# tarjeta-v7.net
KiCad netlist of a schematic drawn in EAGLE
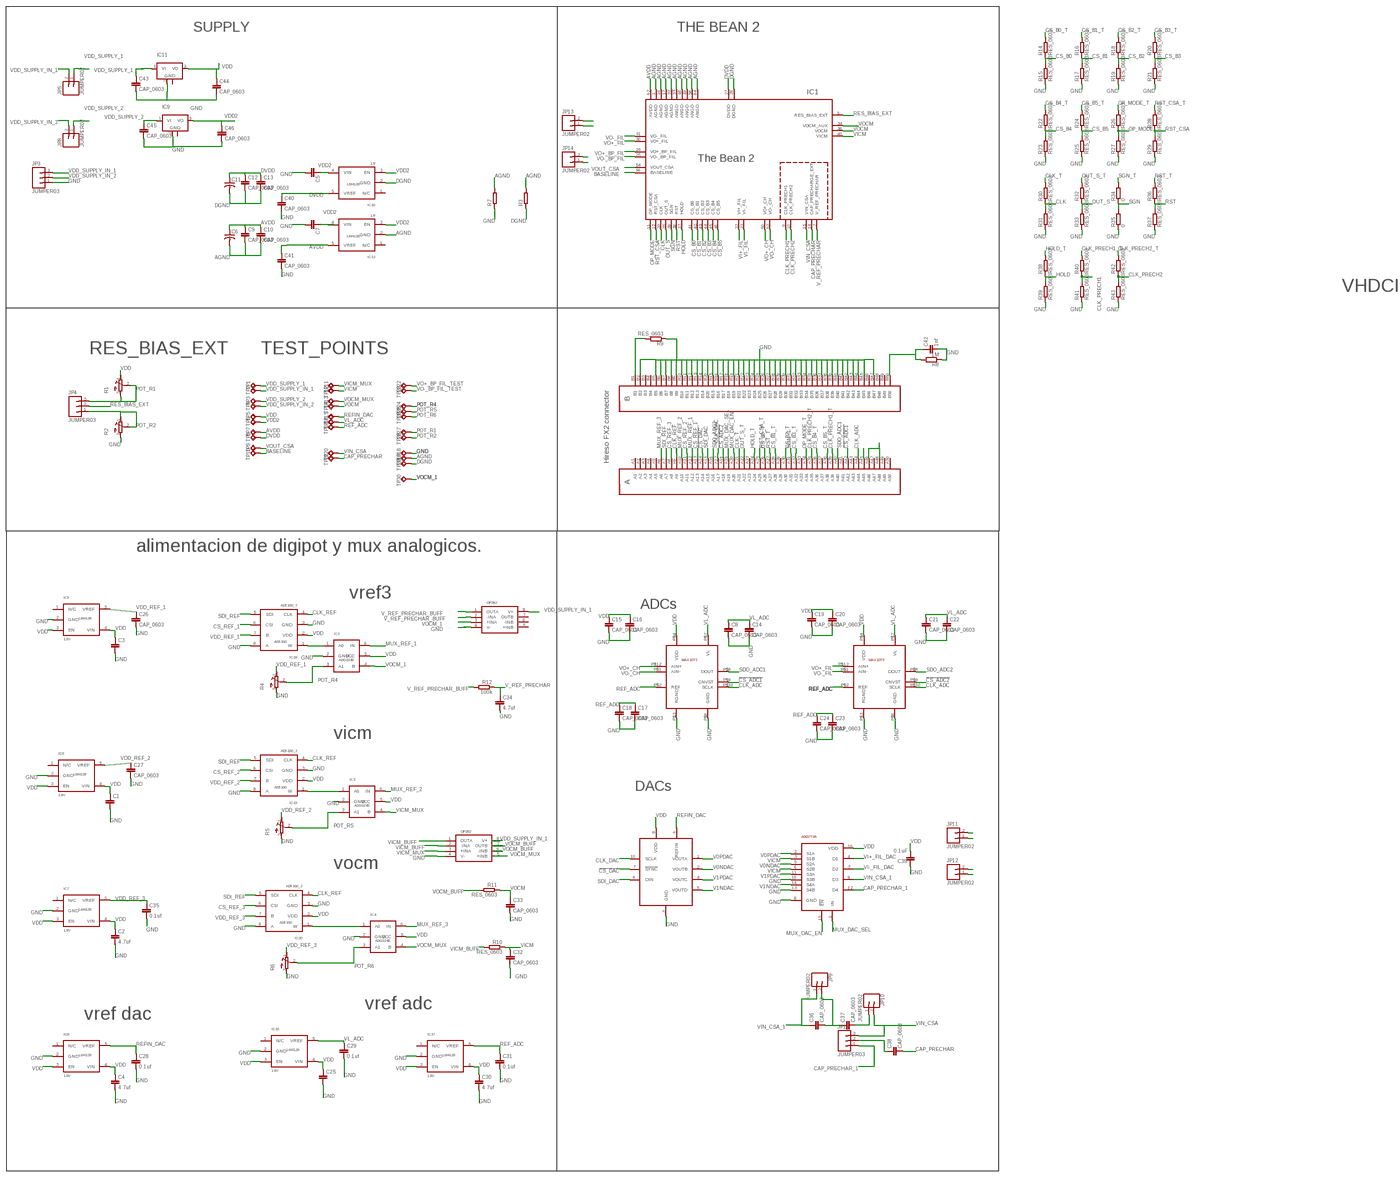
[diagram p0: schematic, sheet 1, overview]
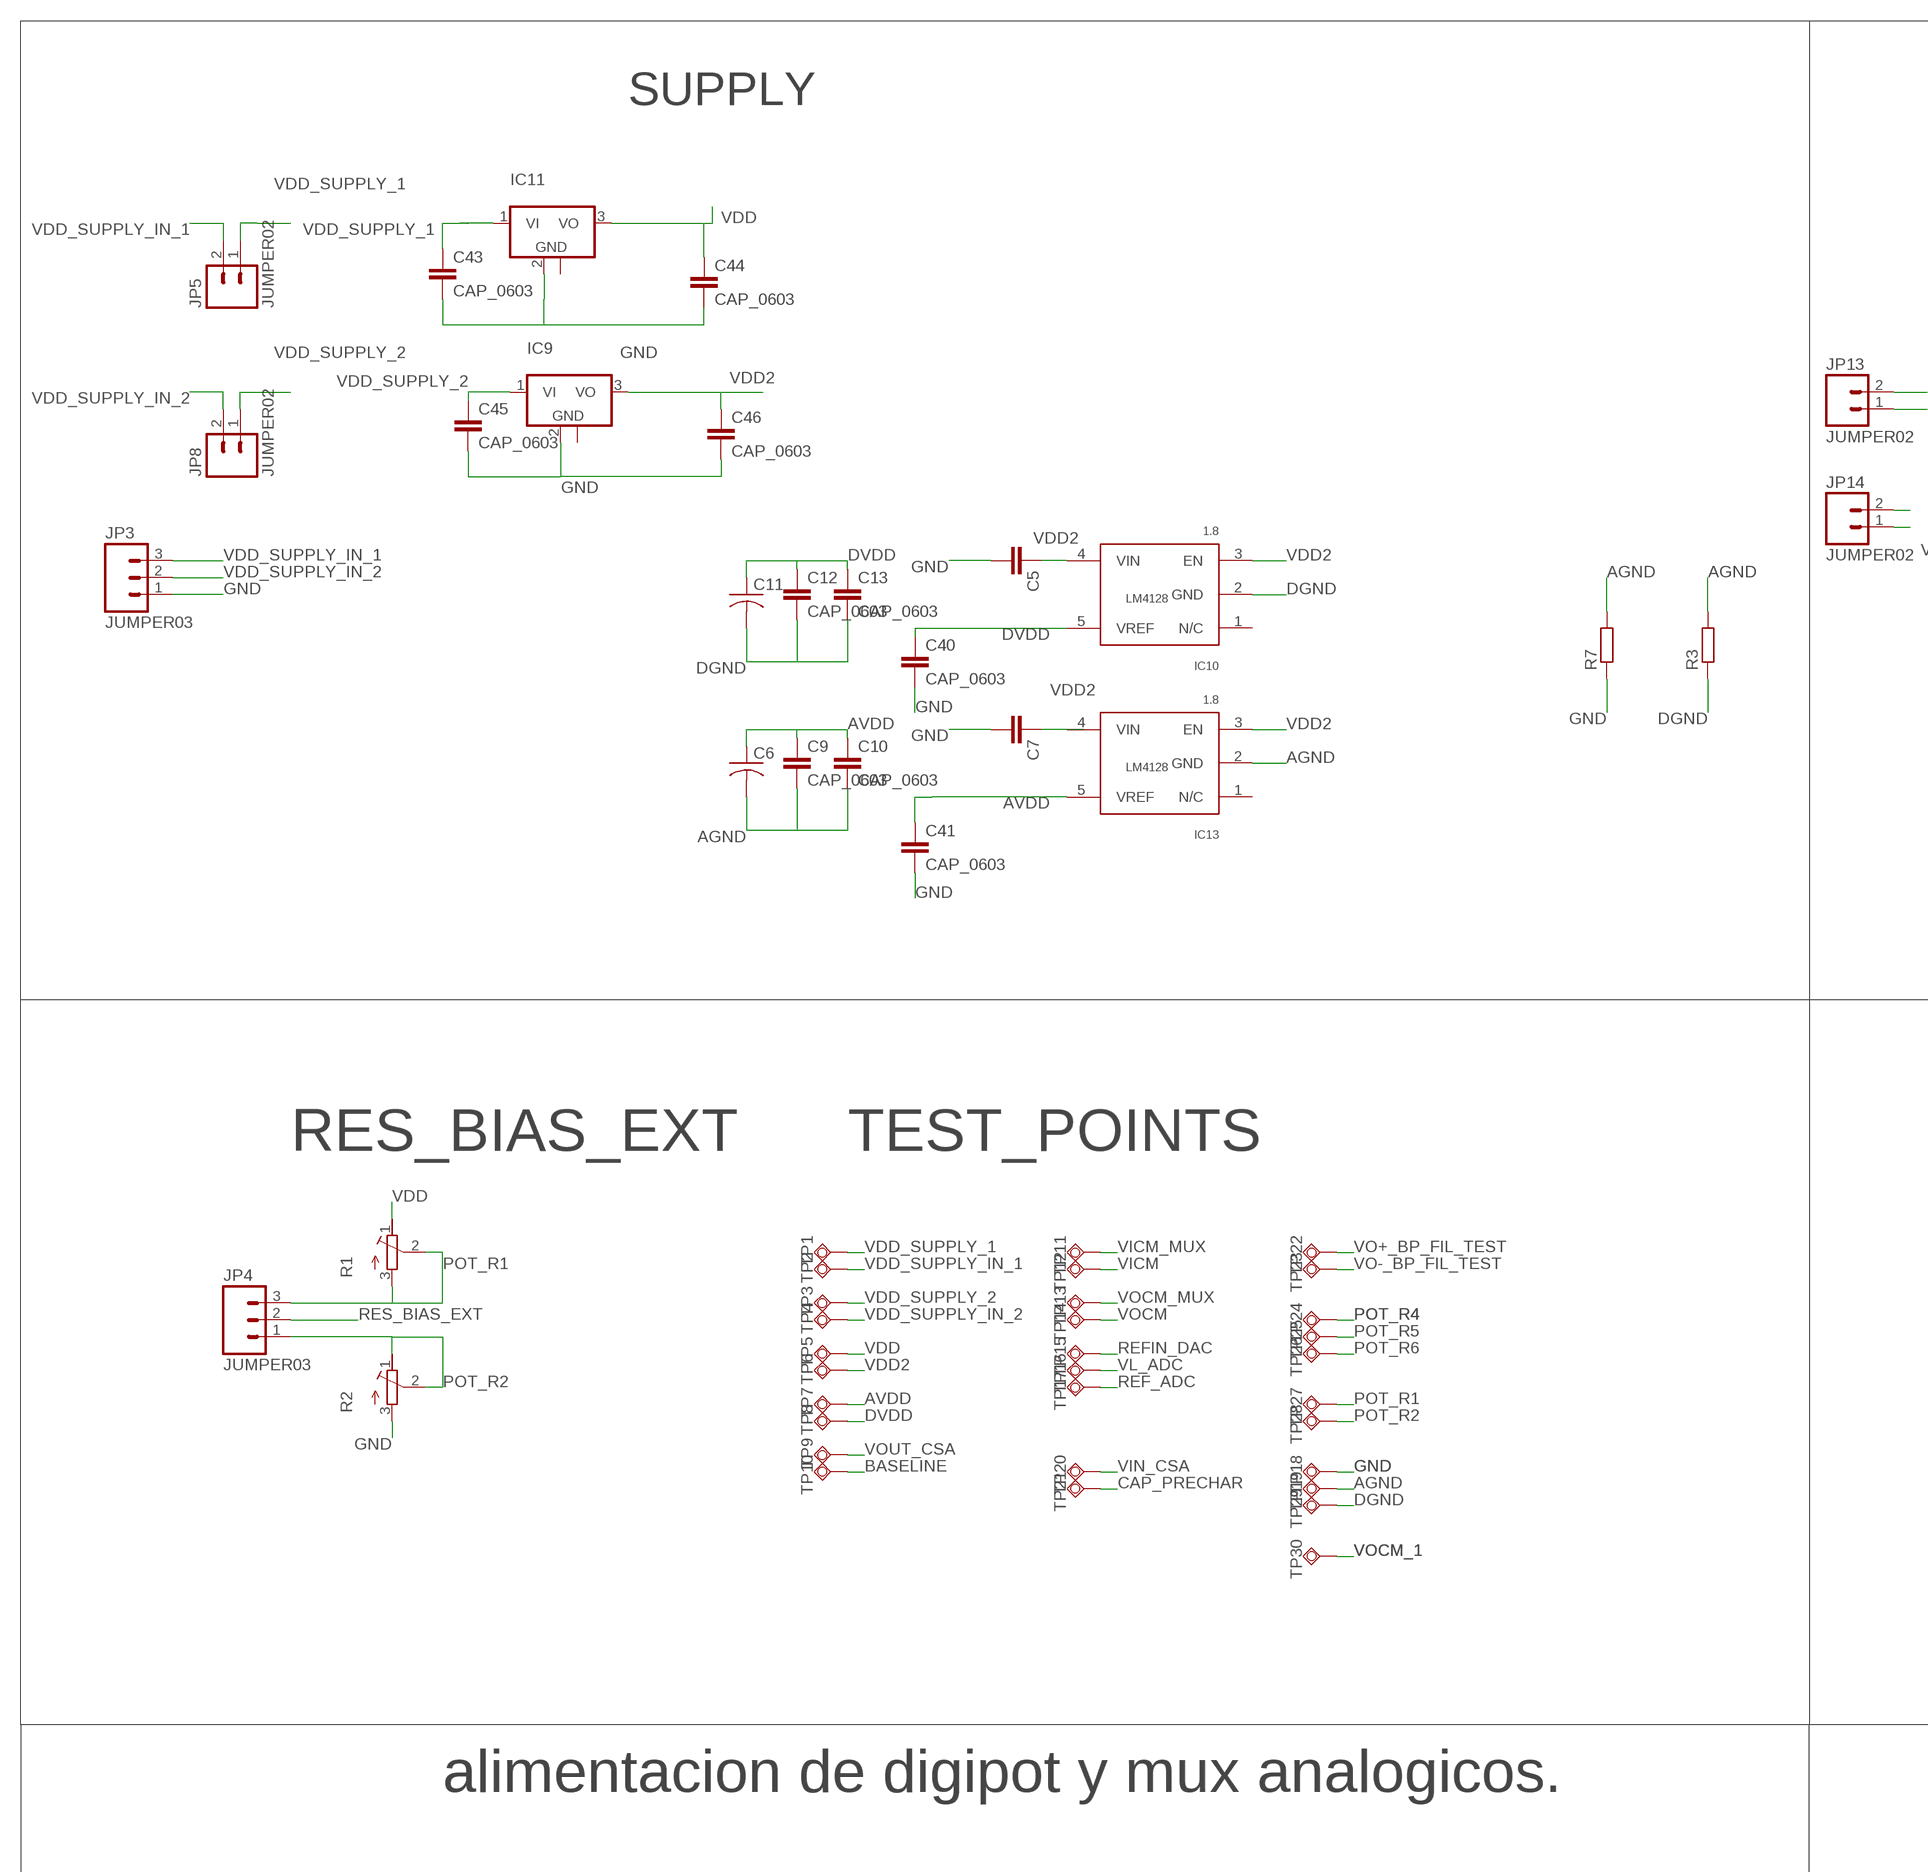
[diagram p1: schematic, sheet 1, part 1 of 4]
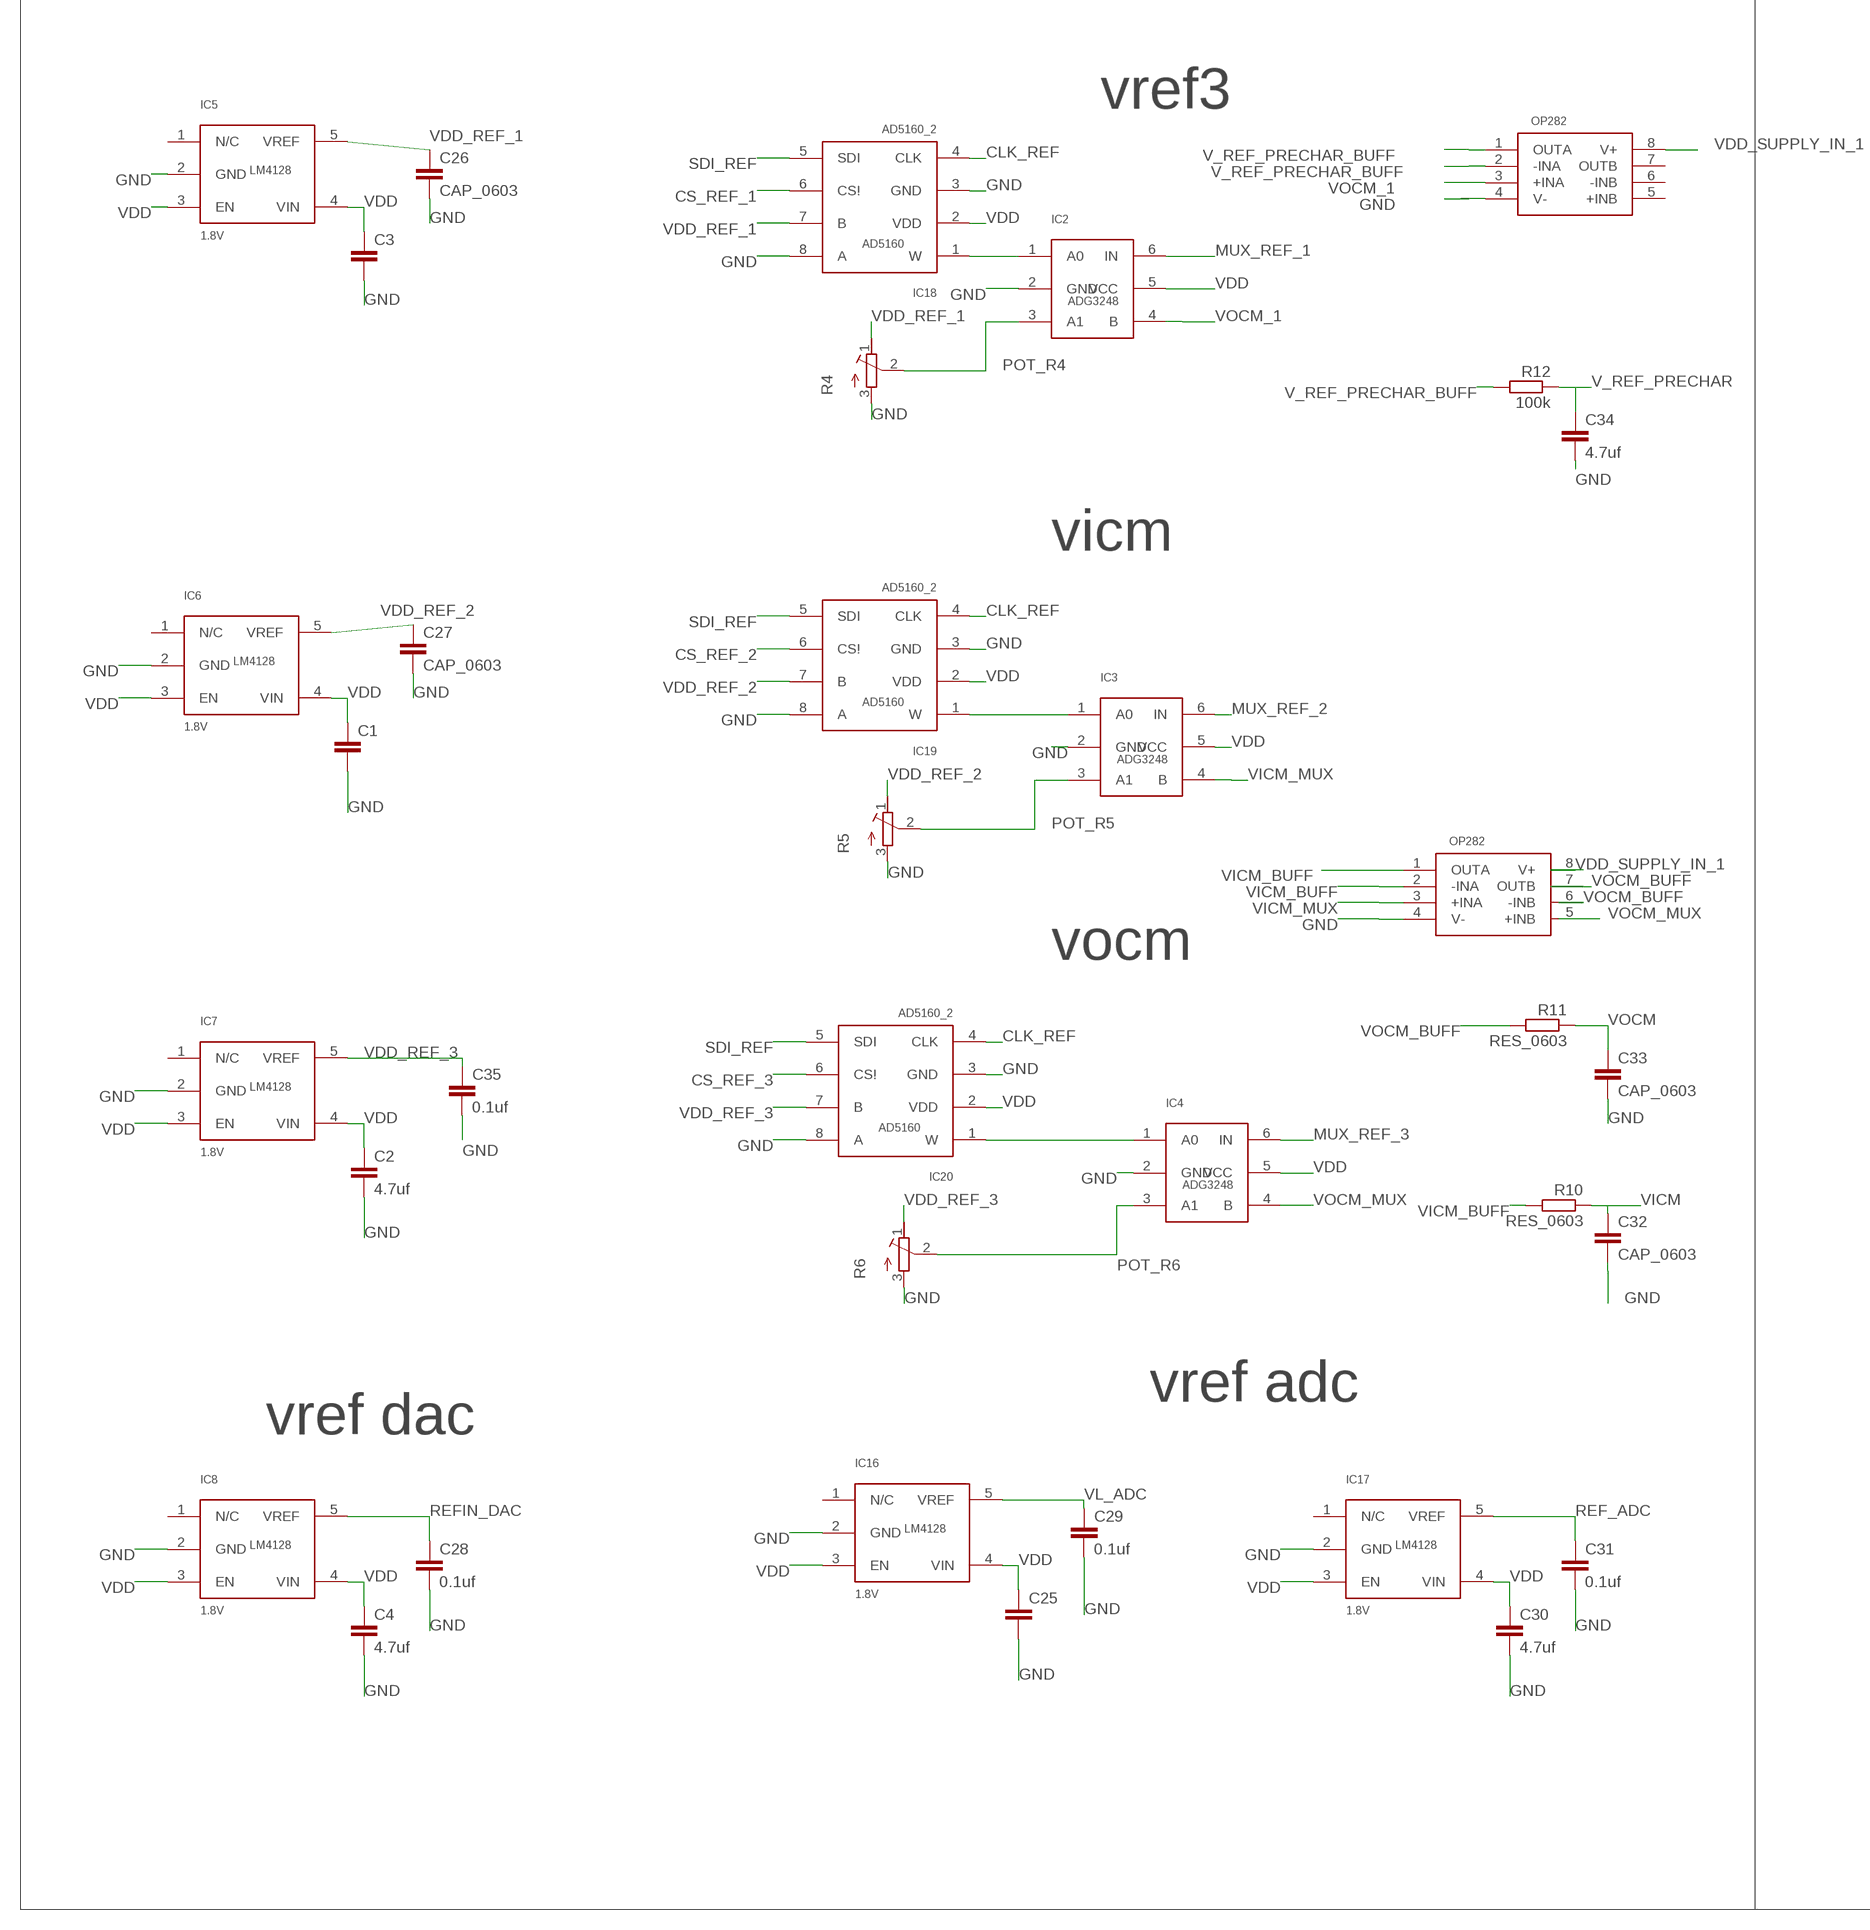
[diagram p2: schematic, sheet 1, part 2 of 4]
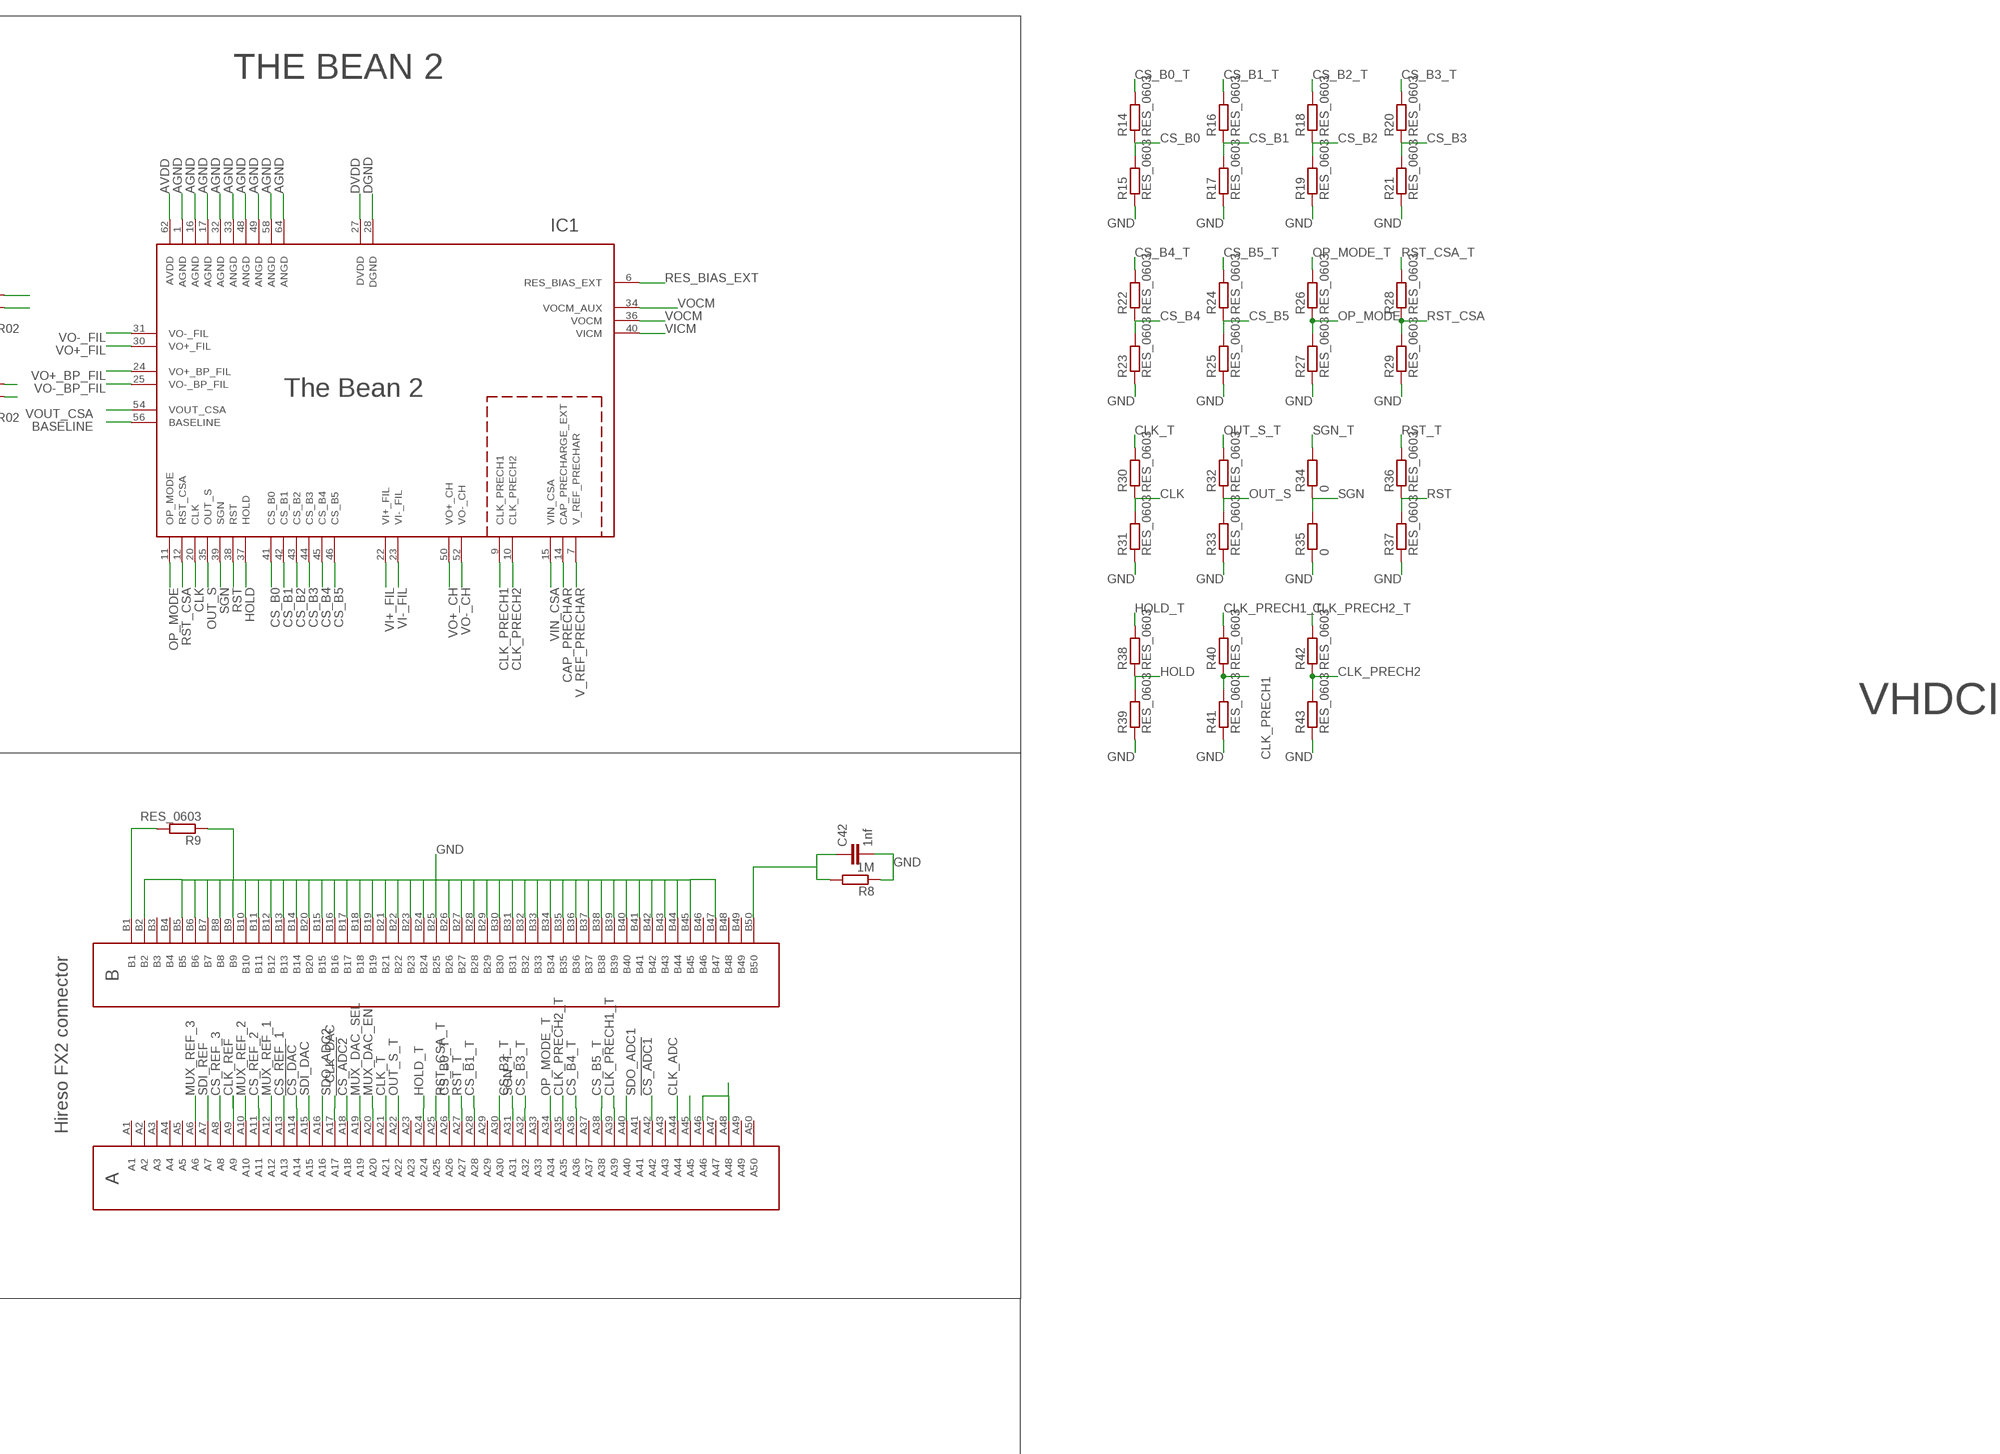
[diagram p3: schematic, sheet 1, part 3 of 4]
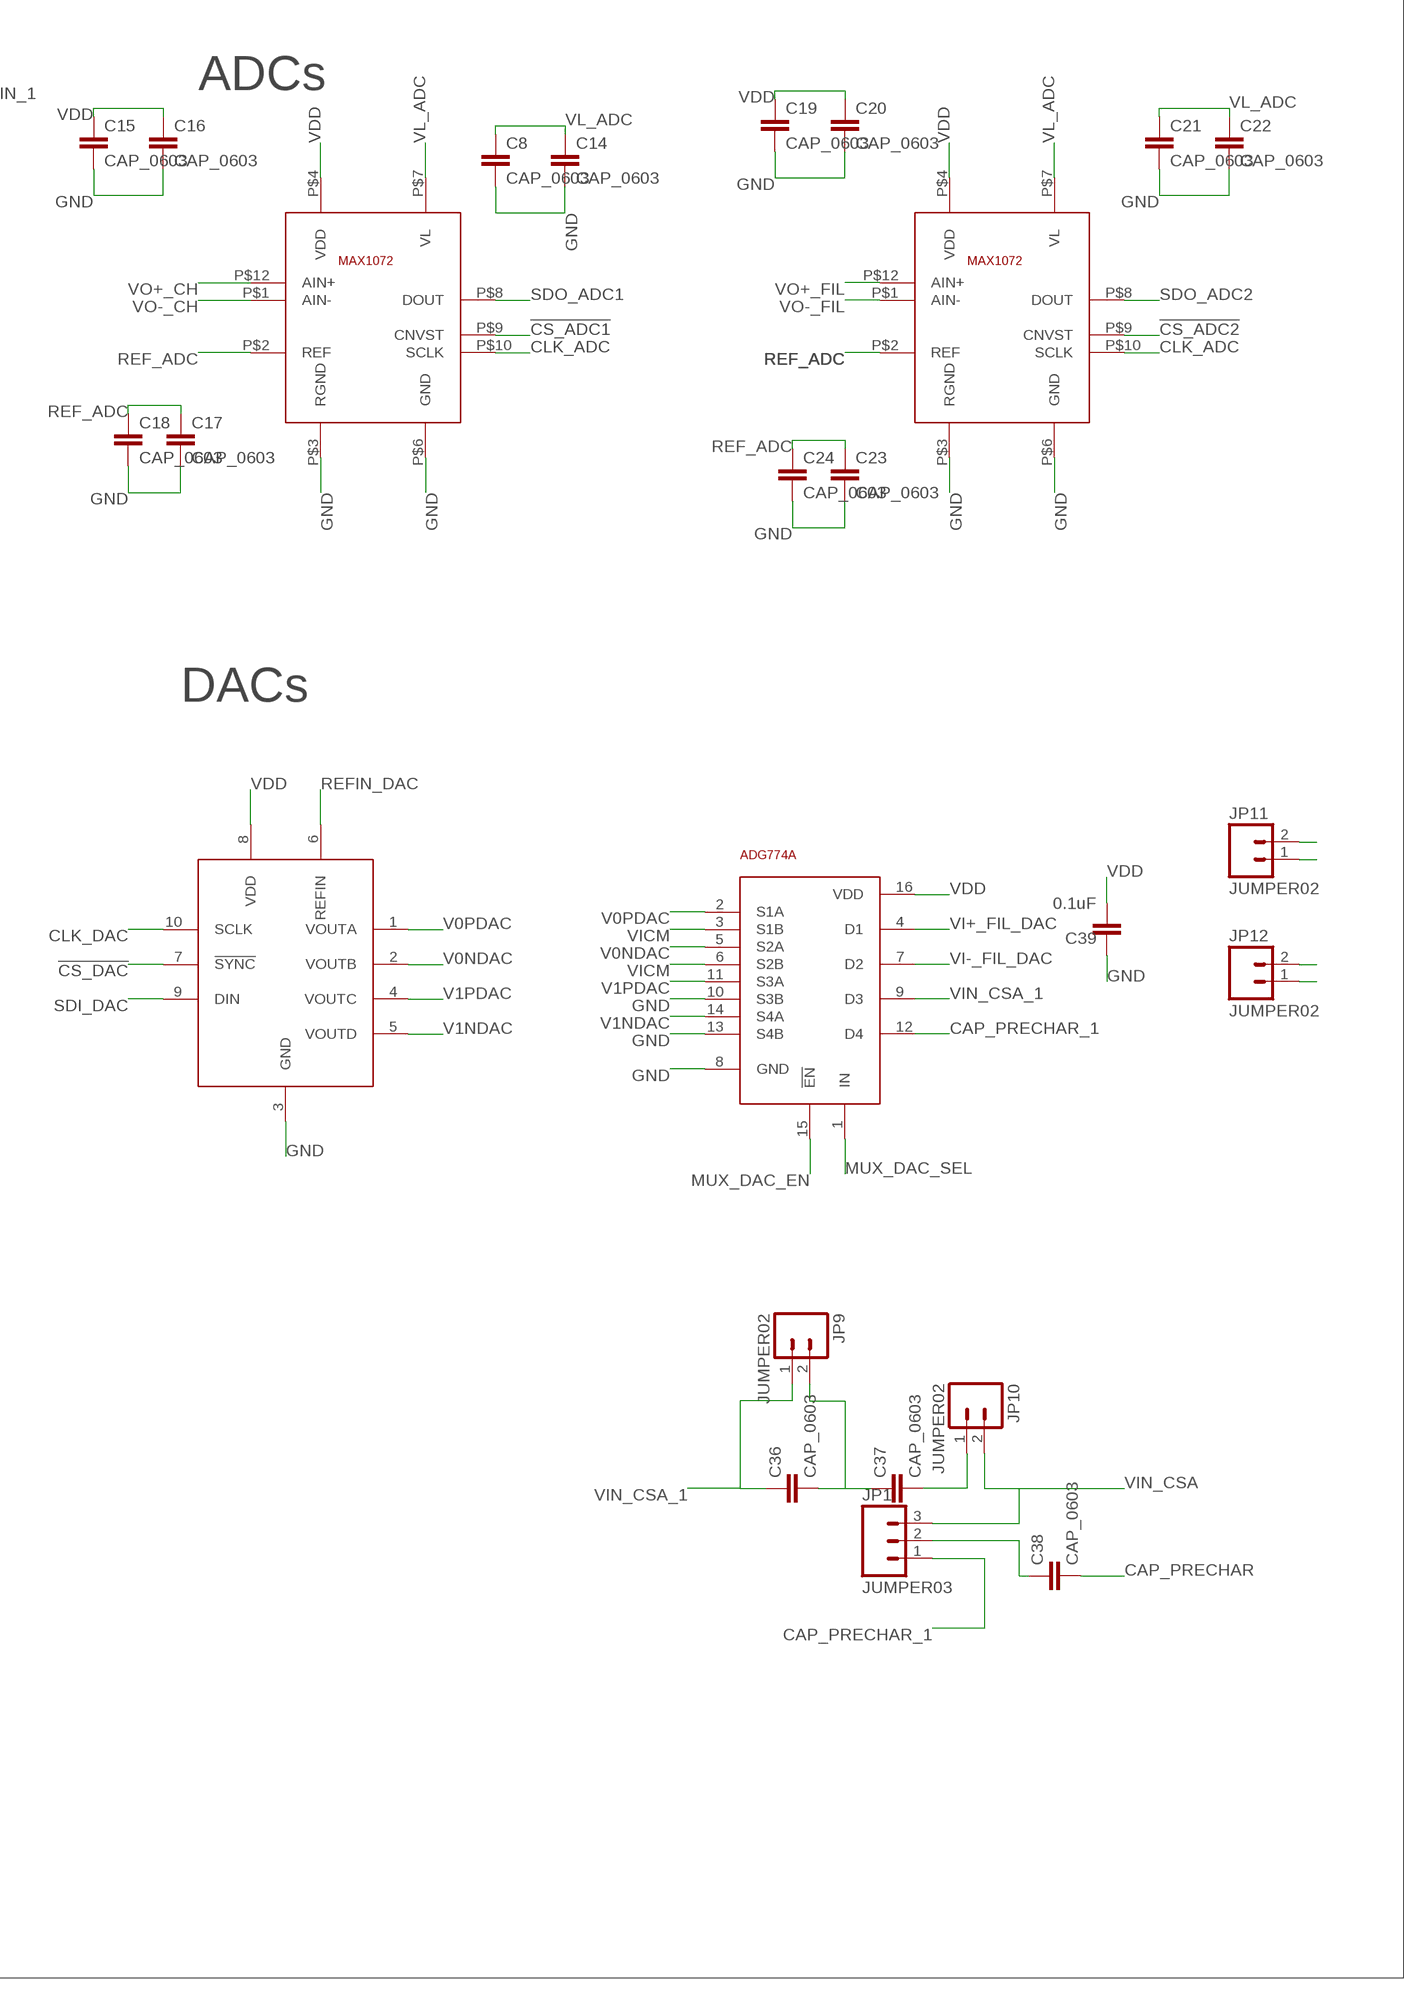
[diagram p4: schematic, sheet 1, part 4 of 4]

(export (version "E")
  (design (tool "Eeschema 10.0.6"))
  (components
    (comp (ref "C1")
      (value "CAP_0402")
      (footprint "eagle-import:C0402")
      (libsource (lib "eagle-import") (part "CAP_0402"))
    )
    (comp (ref "C2")
      (value "4.7uf")
      (footprint "eagle-import:C0402")
      (libsource (lib "eagle-import") (part "CAP_0402"))
    )
    (comp (ref "C3")
      (value "CAP_0402")
      (footprint "eagle-import:C0402")
      (libsource (lib "eagle-import") (part "CAP_0402"))
    )
    (comp (ref "C4")
      (value "4.7uf")
      (footprint "eagle-import:C0402")
      (libsource (lib "eagle-import") (part "CAP_0402"))
    )
    (comp (ref "C5")
      (value "CAP_0402")
      (footprint "eagle-import:C0402")
      (libsource (lib "eagle-import") (part "CAP_0402"))
    )
    (comp (ref "C6")
      (value "CAP_0805")
      (footprint "eagle-import:C0805")
      (libsource (lib "eagle-import") (part "CAP_0805"))
    )
    (comp (ref "C7")
      (value "CAP_0402")
      (footprint "eagle-import:C0402")
      (libsource (lib "eagle-import") (part "CAP_0402"))
    )
    (comp (ref "C8")
      (value "CAP_0603")
      (footprint "eagle-import:C0603")
      (libsource (lib "eagle-import") (part "CAP_0603"))
    )
    (comp (ref "C9")
      (value "CAP_0603")
      (footprint "eagle-import:C0603")
      (libsource (lib "eagle-import") (part "CAP_0603"))
    )
    (comp (ref "C10")
      (value "CAP_0603")
      (footprint "eagle-import:C0603")
      (libsource (lib "eagle-import") (part "CAP_0603"))
    )
    (comp (ref "C11")
      (value "CAP_0805")
      (footprint "eagle-import:C0805")
      (libsource (lib "eagle-import") (part "CAP_0805"))
    )
    (comp (ref "C12")
      (value "CAP_0603")
      (footprint "eagle-import:C0603")
      (libsource (lib "eagle-import") (part "CAP_0603"))
    )
    (comp (ref "C13")
      (value "CAP_0603")
      (footprint "eagle-import:C0603")
      (libsource (lib "eagle-import") (part "CAP_0603"))
    )
    (comp (ref "C14")
      (value "CAP_0603")
      (footprint "eagle-import:C0603")
      (libsource (lib "eagle-import") (part "CAP_0603"))
    )
    (comp (ref "C15")
      (value "CAP_0603")
      (footprint "eagle-import:C0603")
      (libsource (lib "eagle-import") (part "CAP_0603"))
    )
    (comp (ref "C16")
      (value "CAP_0603")
      (footprint "eagle-import:C0603")
      (libsource (lib "eagle-import") (part "CAP_0603"))
    )
    (comp (ref "C17")
      (value "CAP_0603")
      (footprint "eagle-import:C0603")
      (libsource (lib "eagle-import") (part "CAP_0603"))
    )
    (comp (ref "C18")
      (value "CAP_0603")
      (footprint "eagle-import:C0603")
      (libsource (lib "eagle-import") (part "CAP_0603"))
    )
    (comp (ref "C19")
      (value "CAP_0603")
      (footprint "eagle-import:C0603")
      (libsource (lib "eagle-import") (part "CAP_0603"))
    )
    (comp (ref "C20")
      (value "CAP_0603")
      (footprint "eagle-import:C0603")
      (libsource (lib "eagle-import") (part "CAP_0603"))
    )
    (comp (ref "C21")
      (value "CAP_0603")
      (footprint "eagle-import:C0603")
      (libsource (lib "eagle-import") (part "CAP_0603"))
    )
    (comp (ref "C22")
      (value "CAP_0603")
      (footprint "eagle-import:C0603")
      (libsource (lib "eagle-import") (part "CAP_0603"))
    )
    (comp (ref "C23")
      (value "CAP_0603")
      (footprint "eagle-import:C0603")
      (libsource (lib "eagle-import") (part "CAP_0603"))
    )
    (comp (ref "C24")
      (value "CAP_0603")
      (footprint "eagle-import:C0603")
      (libsource (lib "eagle-import") (part "CAP_0603"))
    )
    (comp (ref "C25")
      (value "CAP_0402")
      (footprint "eagle-import:C0402")
      (libsource (lib "eagle-import") (part "CAP_0402"))
    )
    (comp (ref "C26")
      (value "CAP_0603")
      (footprint "eagle-import:C0603")
      (libsource (lib "eagle-import") (part "CAP_0603"))
    )
    (comp (ref "C27")
      (value "CAP_0603")
      (footprint "eagle-import:C0603")
      (libsource (lib "eagle-import") (part "CAP_0603"))
    )
    (comp (ref "C28")
      (value "0.1uf")
      (footprint "eagle-import:C0603")
      (libsource (lib "eagle-import") (part "CAP_0603"))
    )
    (comp (ref "C29")
      (value "0.1uf")
      (footprint "eagle-import:C0603")
      (libsource (lib "eagle-import") (part "CAP_0603"))
    )
    (comp (ref "C30")
      (value "4.7uf")
      (footprint "eagle-import:C0402")
      (libsource (lib "eagle-import") (part "CAP_0402"))
    )
    (comp (ref "C31")
      (value "0.1uf")
      (footprint "eagle-import:C0603")
      (libsource (lib "eagle-import") (part "CAP_0603"))
    )
    (comp (ref "C32")
      (value "CAP_0603")
      (footprint "eagle-import:C0603")
      (libsource (lib "eagle-import") (part "CAP_0603"))
    )
    (comp (ref "C33")
      (value "CAP_0603")
      (footprint "eagle-import:C0603")
      (libsource (lib "eagle-import") (part "CAP_0603"))
    )
    (comp (ref "C34")
      (value "4.7uf")
      (footprint "eagle-import:C0603")
      (libsource (lib "eagle-import") (part "CAP_0603"))
    )
    (comp (ref "C35")
      (value "0.1uf")
      (footprint "eagle-import:C0603")
      (libsource (lib "eagle-import") (part "CAP_0603"))
    )
    (comp (ref "C36")
      (value "CAP_0603")
      (footprint "eagle-import:C0603")
      (libsource (lib "eagle-import") (part "CAP_0603"))
    )
    (comp (ref "C37")
      (value "CAP_0603")
      (footprint "eagle-import:C0603")
      (libsource (lib "eagle-import") (part "CAP_0603"))
    )
    (comp (ref "C38")
      (value "CAP_0603")
      (footprint "eagle-import:C0603")
      (libsource (lib "eagle-import") (part "CAP_0603"))
    )
    (comp (ref "C39")
      (value "0.1uF")
      (footprint "eagle-import:C0603")
      (libsource (lib "eagle-import") (part "CAP_0603"))
    )
    (comp (ref "C40")
      (value "CAP_0603")
      (footprint "eagle-import:C0603")
      (libsource (lib "eagle-import") (part "CAP_0603"))
    )
    (comp (ref "C41")
      (value "CAP_0603")
      (footprint "eagle-import:C0603")
      (libsource (lib "eagle-import") (part "CAP_0603"))
    )
    (comp (ref "C42")
      (value "1nf")
      (footprint "eagle-import:C0603")
      (libsource (lib "eagle-import") (part "CAP_0603"))
    )
    (comp (ref "C43")
      (value "CAP_0603")
      (footprint "eagle-import:C0603")
      (libsource (lib "eagle-import") (part "CAP_0603"))
    )
    (comp (ref "C44")
      (value "CAP_0603")
      (footprint "eagle-import:C0603")
      (libsource (lib "eagle-import") (part "CAP_0603"))
    )
    (comp (ref "C45")
      (value "CAP_0603")
      (footprint "eagle-import:C0603")
      (libsource (lib "eagle-import") (part "CAP_0603"))
    )
    (comp (ref "C46")
      (value "CAP_0603")
      (footprint "eagle-import:C0603")
      (libsource (lib "eagle-import") (part "CAP_0603"))
    )
    (comp (ref "IC1")
      (value "THE_BEAN_2")
      (footprint "eagle-import:QFN64")
      (libsource (lib "eagle-import") (part "THE_BEAN_2"))
    )
    (comp (ref "IC2")
      (value "ADG3248")
      (footprint "eagle-import:SC70")
      (libsource (lib "eagle-import") (part "ADG3248"))
    )
    (comp (ref "IC3")
      (value "ADG3248")
      (footprint "eagle-import:SC70")
      (libsource (lib "eagle-import") (part "ADG3248"))
    )
    (comp (ref "IC4")
      (value "ADG3248")
      (footprint "eagle-import:SC70")
      (libsource (lib "eagle-import") (part "ADG3248"))
    )
    (comp (ref "IC5")
      (value "1.8V")
      (footprint "eagle-import:SOT23-5L_2")
      (libsource (lib "eagle-import") (part "LM4128_2"))
    )
    (comp (ref "IC6")
      (value "1.8V")
      (footprint "eagle-import:SOT23-5L_2")
      (libsource (lib "eagle-import") (part "LM4128_2"))
    )
    (comp (ref "IC7")
      (value "1.8V")
      (footprint "eagle-import:SOT23-5L_2")
      (libsource (lib "eagle-import") (part "LM4128_2"))
    )
    (comp (ref "IC8")
      (value "1.8V")
      (footprint "eagle-import:SOT23-5L_2")
      (libsource (lib "eagle-import") (part "LM4128_2"))
    )
    (comp (ref "IC9")
      (value "UA78M33DCY")
      (footprint "eagle-import:SOT223")
      (libsource (lib "eagle-import") (part "UA78MDCY33"))
    )
    (comp (ref "IC10")
      (value "1.8")
      (footprint "eagle-import:SOT23-5L_2")
      (libsource (lib "eagle-import") (part "LM4128_2"))
    )
    (comp (ref "IC11")
      (value "UA78M33DCY")
      (footprint "eagle-import:SOT223")
      (libsource (lib "eagle-import") (part "UA78MDCY33"))
    )
    (comp (ref "IC12")
      (value "OP282")
      (footprint "eagle-import:MSOP8")
      (libsource (lib "eagle-import") (part "OP282"))
    )
    (comp (ref "IC13")
      (value "1.8")
      (footprint "eagle-import:SOT23-5L_2")
      (libsource (lib "eagle-import") (part "LM4128_2"))
    )
    (comp (ref "IC14")
      (value "OP282")
      (footprint "eagle-import:MSOP8")
      (libsource (lib "eagle-import") (part "OP282"))
    )
    (comp (ref "IC16")
      (value "1.8V")
      (footprint "eagle-import:SOT23-5L_2")
      (libsource (lib "eagle-import") (part "LM4128_2"))
    )
    (comp (ref "IC17")
      (value "1.8V")
      (footprint "eagle-import:SOT23-5L_2")
      (libsource (lib "eagle-import") (part "LM4128_2"))
    )
    (comp (ref "IC18")
      (value "AD5160_2")
      (footprint "eagle-import:SOT23-8_2")
      (libsource (lib "eagle-import") (part "AD5160_2"))
    )
    (comp (ref "IC19")
      (value "AD5160_2")
      (footprint "eagle-import:SOT23-8_2")
      (libsource (lib "eagle-import") (part "AD5160_2"))
    )
    (comp (ref "IC20")
      (value "AD5160_2")
      (footprint "eagle-import:SOT23-8_2")
      (libsource (lib "eagle-import") (part "AD5160_2"))
    )
    (comp (ref "IC21")
      (value "ADG774A")
      (footprint "eagle-import:QSOP16")
      (libsource (lib "eagle-import") (part "ADG774A"))
    )
    (comp (ref "IC22")
      (value "MAX1072")
      (footprint "eagle-import:TQFN12")
      (libsource (lib "eagle-import") (part "MAX1072"))
    )
    (comp (ref "IC23")
      (value "DAC7554")
      (footprint "eagle-import:MSOP10")
      (libsource (lib "eagle-import") (part "DAC7554"))
    )
    (comp (ref "J1")
      (value "HIRESO_FX_CONNECTOR")
      (footprint "eagle-import:FX2-100S-1.27")
      (libsource (lib "eagle-import") (part "HIRESO_FX_CONNECTOR"))
    )
    (comp (ref "JP1")
      (value "JUMPER03")
      (footprint "eagle-import:1X03")
      (libsource (lib "eagle-import") (part "JUMPER03"))
    )
    (comp (ref "JP3")
      (value "JUMPER03")
      (footprint "eagle-import:1X03")
      (libsource (lib "eagle-import") (part "JUMPER03"))
    )
    (comp (ref "JP4")
      (value "JUMPER03")
      (footprint "eagle-import:1X03")
      (libsource (lib "eagle-import") (part "JUMPER03"))
    )
    (comp (ref "JP5")
      (value "JUMPER02")
      (footprint "eagle-import:1X02")
      (libsource (lib "eagle-import") (part "JUMPER02"))
    )
    (comp (ref "JP8")
      (value "JUMPER02")
      (footprint "eagle-import:1X02")
      (libsource (lib "eagle-import") (part "JUMPER02"))
    )
    (comp (ref "JP9")
      (value "JUMPER02")
      (footprint "eagle-import:1X02")
      (libsource (lib "eagle-import") (part "JUMPER02"))
    )
    (comp (ref "JP10")
      (value "JUMPER02")
      (footprint "eagle-import:1X02")
      (libsource (lib "eagle-import") (part "JUMPER02"))
    )
    (comp (ref "JP11")
      (value "JUMPER02")
      (footprint "eagle-import:1X02")
      (libsource (lib "eagle-import") (part "JUMPER02"))
    )
    (comp (ref "JP12")
      (value "JUMPER02")
      (footprint "eagle-import:1X02")
      (libsource (lib "eagle-import") (part "JUMPER02"))
    )
    (comp (ref "JP13")
      (value "JUMPER02")
      (footprint "eagle-import:1X02")
      (libsource (lib "eagle-import") (part "JUMPER02"))
    )
    (comp (ref "JP14")
      (value "JUMPER02")
      (footprint "eagle-import:1X02")
      (libsource (lib "eagle-import") (part "JUMPER02"))
    )
    (comp (ref "R1")
      (value "TRIMMER_ST5")
      (footprint "eagle-import:ST-5EW")
      (libsource (lib "eagle-import") (part "TRIMMER_ST5"))
    )
    (comp (ref "R2")
      (value "TRIMMER_ST5")
      (footprint "eagle-import:ST-5EW")
      (libsource (lib "eagle-import") (part "TRIMMER_ST5"))
    )
    (comp (ref "R3")
      (value "RES_0402")
      (footprint "eagle-import:R0402")
      (libsource (lib "eagle-import") (part "RES_0402"))
    )
    (comp (ref "R4")
      (value "TRIMMER_ST5")
      (footprint "eagle-import:ST-5EW")
      (libsource (lib "eagle-import") (part "TRIMMER_ST5"))
    )
    (comp (ref "R5")
      (value "TRIMMER_ST5")
      (footprint "eagle-import:ST-5EW")
      (libsource (lib "eagle-import") (part "TRIMMER_ST5"))
    )
    (comp (ref "R6")
      (value "TRIMMER_ST5")
      (footprint "eagle-import:ST-5EW")
      (libsource (lib "eagle-import") (part "TRIMMER_ST5"))
    )
    (comp (ref "R7")
      (value "RES_0402")
      (footprint "eagle-import:R0402")
      (libsource (lib "eagle-import") (part "RES_0402"))
    )
    (comp (ref "R8")
      (value "1M")
      (footprint "eagle-import:R0603")
      (libsource (lib "eagle-import") (part "RES_0603"))
    )
    (comp (ref "R9")
      (value "RES_0603")
      (footprint "eagle-import:R0603")
      (libsource (lib "eagle-import") (part "RES_0603"))
    )
    (comp (ref "R10")
      (value "RES_0603")
      (footprint "eagle-import:R0603")
      (libsource (lib "eagle-import") (part "RES_0603"))
    )
    (comp (ref "R11")
      (value "RES_0603")
      (footprint "eagle-import:R0603")
      (libsource (lib "eagle-import") (part "RES_0603"))
    )
    (comp (ref "R12")
      (value "100k")
      (footprint "eagle-import:R0603")
      (libsource (lib "eagle-import") (part "RES_0603"))
    )
    (comp (ref "R14")
      (value "RES_0603")
      (footprint "eagle-import:R0603")
      (libsource (lib "eagle-import") (part "RES_0603"))
    )
    (comp (ref "R15")
      (value "RES_0603")
      (footprint "eagle-import:R0603")
      (libsource (lib "eagle-import") (part "RES_0603"))
    )
    (comp (ref "R16")
      (value "RES_0603")
      (footprint "eagle-import:R0603")
      (libsource (lib "eagle-import") (part "RES_0603"))
    )
    (comp (ref "R17")
      (value "RES_0603")
      (footprint "eagle-import:R0603")
      (libsource (lib "eagle-import") (part "RES_0603"))
    )
    (comp (ref "R18")
      (value "RES_0603")
      (footprint "eagle-import:R0603")
      (libsource (lib "eagle-import") (part "RES_0603"))
    )
    (comp (ref "R19")
      (value "RES_0603")
      (footprint "eagle-import:R0603")
      (libsource (lib "eagle-import") (part "RES_0603"))
    )
    (comp (ref "R20")
      (value "RES_0603")
      (footprint "eagle-import:R0603")
      (libsource (lib "eagle-import") (part "RES_0603"))
    )
    (comp (ref "R21")
      (value "RES_0603")
      (footprint "eagle-import:R0603")
      (libsource (lib "eagle-import") (part "RES_0603"))
    )
    (comp (ref "R22")
      (value "RES_0603")
      (footprint "eagle-import:R0603")
      (libsource (lib "eagle-import") (part "RES_0603"))
    )
    (comp (ref "R23")
      (value "RES_0603")
      (footprint "eagle-import:R0603")
      (libsource (lib "eagle-import") (part "RES_0603"))
    )
    (comp (ref "R24")
      (value "RES_0603")
      (footprint "eagle-import:R0603")
      (libsource (lib "eagle-import") (part "RES_0603"))
    )
    (comp (ref "R25")
      (value "RES_0603")
      (footprint "eagle-import:R0603")
      (libsource (lib "eagle-import") (part "RES_0603"))
    )
    (comp (ref "R26")
      (value "RES_0603")
      (footprint "eagle-import:R0603")
      (libsource (lib "eagle-import") (part "RES_0603"))
    )
    (comp (ref "R27")
      (value "RES_0603")
      (footprint "eagle-import:R0603")
      (libsource (lib "eagle-import") (part "RES_0603"))
    )
    (comp (ref "R28")
      (value "RES_0603")
      (footprint "eagle-import:R0603")
      (libsource (lib "eagle-import") (part "RES_0603"))
    )
    (comp (ref "R29")
      (value "RES_0603")
      (footprint "eagle-import:R0603")
      (libsource (lib "eagle-import") (part "RES_0603"))
    )
    (comp (ref "R30")
      (value "RES_0603")
      (footprint "eagle-import:R0603")
      (libsource (lib "eagle-import") (part "RES_0603"))
    )
    (comp (ref "R31")
      (value "RES_0603")
      (footprint "eagle-import:R0603")
      (libsource (lib "eagle-import") (part "RES_0603"))
    )
    (comp (ref "R32")
      (value "RES_0603")
      (footprint "eagle-import:R0603")
      (libsource (lib "eagle-import") (part "RES_0603"))
    )
    (comp (ref "R33")
      (value "RES_0603")
      (footprint "eagle-import:R0603")
      (libsource (lib "eagle-import") (part "RES_0603"))
    )
    (comp (ref "R34")
      (value "0")
      (footprint "eagle-import:R0603")
      (libsource (lib "eagle-import") (part "RES_0603"))
    )
    (comp (ref "R35")
      (value "0")
      (footprint "eagle-import:R0603")
      (libsource (lib "eagle-import") (part "RES_0603"))
    )
    (comp (ref "R36")
      (value "RES_0603")
      (footprint "eagle-import:R0603")
      (libsource (lib "eagle-import") (part "RES_0603"))
    )
    (comp (ref "R37")
      (value "RES_0603")
      (footprint "eagle-import:R0603")
      (libsource (lib "eagle-import") (part "RES_0603"))
    )
    (comp (ref "R38")
      (value "RES_0603")
      (footprint "eagle-import:R0603")
      (libsource (lib "eagle-import") (part "RES_0603"))
    )
    (comp (ref "R39")
      (value "RES_0603")
      (footprint "eagle-import:R0603")
      (libsource (lib "eagle-import") (part "RES_0603"))
    )
    (comp (ref "R40")
      (value "RES_0603")
      (footprint "eagle-import:R0603")
      (libsource (lib "eagle-import") (part "RES_0603"))
    )
    (comp (ref "R41")
      (value "RES_0603")
      (footprint "eagle-import:R0603")
      (libsource (lib "eagle-import") (part "RES_0603"))
    )
    (comp (ref "R42")
      (value "RES_0603")
      (footprint "eagle-import:R0603")
      (libsource (lib "eagle-import") (part "RES_0603"))
    )
    (comp (ref "R43")
      (value "RES_0603")
      (footprint "eagle-import:R0603")
      (libsource (lib "eagle-import") (part "RES_0603"))
    )
    (comp (ref "TP1")
      (value "TEST_POINT")
      (footprint "eagle-import:TP")
      (libsource (lib "eagle-import") (part "TEST_POINT"))
    )
    (comp (ref "TP2")
      (value "TEST_POINT")
      (footprint "eagle-import:TP")
      (libsource (lib "eagle-import") (part "TEST_POINT"))
    )
    (comp (ref "TP3")
      (value "TEST_POINT")
      (footprint "eagle-import:TP")
      (libsource (lib "eagle-import") (part "TEST_POINT"))
    )
    (comp (ref "TP4")
      (value "TEST_POINT")
      (footprint "eagle-import:TP")
      (libsource (lib "eagle-import") (part "TEST_POINT"))
    )
    (comp (ref "TP5")
      (value "TEST_POINT")
      (footprint "eagle-import:TP")
      (libsource (lib "eagle-import") (part "TEST_POINT"))
    )
    (comp (ref "TP6")
      (value "TEST_POINT")
      (footprint "eagle-import:TP")
      (libsource (lib "eagle-import") (part "TEST_POINT"))
    )
    (comp (ref "TP7")
      (value "TEST_POINT")
      (footprint "eagle-import:TP")
      (libsource (lib "eagle-import") (part "TEST_POINT"))
    )
    (comp (ref "TP8")
      (value "TEST_POINT")
      (footprint "eagle-import:TP")
      (libsource (lib "eagle-import") (part "TEST_POINT"))
    )
    (comp (ref "TP9")
      (value "TEST_POINT")
      (footprint "eagle-import:TP")
      (libsource (lib "eagle-import") (part "TEST_POINT"))
    )
    (comp (ref "TP10")
      (value "TEST_POINT")
      (footprint "eagle-import:TP")
      (libsource (lib "eagle-import") (part "TEST_POINT"))
    )
    (comp (ref "TP11")
      (value "TEST_POINT")
      (footprint "eagle-import:TP")
      (libsource (lib "eagle-import") (part "TEST_POINT"))
    )
    (comp (ref "TP12")
      (value "TEST_POINT")
      (footprint "eagle-import:TP")
      (libsource (lib "eagle-import") (part "TEST_POINT"))
    )
    (comp (ref "TP13")
      (value "TEST_POINT")
      (footprint "eagle-import:TP")
      (libsource (lib "eagle-import") (part "TEST_POINT"))
    )
    (comp (ref "TP14")
      (value "TEST_POINT")
      (footprint "eagle-import:TP")
      (libsource (lib "eagle-import") (part "TEST_POINT"))
    )
    (comp (ref "TP15")
      (value "TEST_POINT")
      (footprint "eagle-import:TP")
      (libsource (lib "eagle-import") (part "TEST_POINT"))
    )
    (comp (ref "TP16")
      (value "TEST_POINT")
      (footprint "eagle-import:TP")
      (libsource (lib "eagle-import") (part "TEST_POINT"))
    )
    (comp (ref "TP17")
      (value "TEST_POINT")
      (footprint "eagle-import:TP")
      (libsource (lib "eagle-import") (part "TEST_POINT"))
    )
    (comp (ref "TP18")
      (value "TEST_POINT")
      (footprint "eagle-import:TP")
      (libsource (lib "eagle-import") (part "TEST_POINT"))
    )
    (comp (ref "TP19")
      (value "TEST_POINT")
      (footprint "eagle-import:TP")
      (libsource (lib "eagle-import") (part "TEST_POINT"))
    )
    (comp (ref "TP20")
      (value "TEST_POINT")
      (footprint "eagle-import:TP")
      (libsource (lib "eagle-import") (part "TEST_POINT"))
    )
    (comp (ref "TP21")
      (value "TEST_POINT")
      (footprint "eagle-import:TP")
      (libsource (lib "eagle-import") (part "TEST_POINT"))
    )
    (comp (ref "TP22")
      (value "TEST_POINT")
      (footprint "eagle-import:TP")
      (libsource (lib "eagle-import") (part "TEST_POINT"))
    )
    (comp (ref "TP23")
      (value "TEST_POINT")
      (footprint "eagle-import:TP")
      (libsource (lib "eagle-import") (part "TEST_POINT"))
    )
    (comp (ref "TP24")
      (value "TEST_POINT")
      (footprint "eagle-import:TP")
      (libsource (lib "eagle-import") (part "TEST_POINT"))
    )
    (comp (ref "TP25")
      (value "TEST_POINT")
      (footprint "eagle-import:TP")
      (libsource (lib "eagle-import") (part "TEST_POINT"))
    )
    (comp (ref "TP26")
      (value "TEST_POINT")
      (footprint "eagle-import:TP")
      (libsource (lib "eagle-import") (part "TEST_POINT"))
    )
    (comp (ref "TP27")
      (value "TEST_POINT")
      (footprint "eagle-import:TP")
      (libsource (lib "eagle-import") (part "TEST_POINT"))
    )
    (comp (ref "TP28")
      (value "TEST_POINT")
      (footprint "eagle-import:TP")
      (libsource (lib "eagle-import") (part "TEST_POINT"))
    )
    (comp (ref "TP29")
      (value "TEST_POINT")
      (footprint "eagle-import:TP")
      (libsource (lib "eagle-import") (part "TEST_POINT"))
    )
    (comp (ref "TP30")
      (value "TEST_POINT")
      (footprint "eagle-import:TP")
      (libsource (lib "eagle-import") (part "TEST_POINT"))
    )
    (comp (ref "U$5")
      (value "MAX1072")
      (footprint "eagle-import:TQFN12")
      (libsource (lib "eagle-import") (part "MAX1072"))
    )
  )
  (nets
    (net (code "1") (name "/AGND") (class "Default")
      (node (ref "C10") (pin "2") (pinfunction "2_2") (pintype "passive"))
      (node (ref "C6") (pin "2") (pinfunction "2_2") (pintype "passive"))
      (node (ref "C9") (pin "2") (pinfunction "2_2") (pintype "passive"))
      (node (ref "IC1") (pin "1") (pinfunction "AGND_1") (pintype "power_in"))
      (node (ref "IC1") (pin "16") (pinfunction "AGND_16") (pintype "power_in"))
      (node (ref "IC1") (pin "17") (pinfunction "AGND_17") (pintype "power_in"))
      (node (ref "IC1") (pin "32") (pinfunction "AGND_32") (pintype "power_in"))
      (node (ref "IC1") (pin "33") (pinfunction "ANGD_33") (pintype "power_in"))
      (node (ref "IC1") (pin "48") (pinfunction "ANGD_48") (pintype "power_in"))
      (node (ref "IC1") (pin "49") (pinfunction "ANGD_49") (pintype "power_in"))
      (node (ref "IC1") (pin "58") (pinfunction "ANGD_58") (pintype "power_in"))
      (node (ref "IC1") (pin "64") (pinfunction "ANGD_64") (pintype "power_in"))
      (node (ref "IC13") (pin "2") (pinfunction "GND_2") (pintype "bidirectional"))
      (node (ref "R3") (pin "2") (pinfunction "2_2") (pintype "passive"))
      (node (ref "R7") (pin "2") (pinfunction "2_2") (pintype "passive"))
      (node (ref "TP19") (pin "TP") (pinfunction "TP_TP") (pintype "input"))
    )
    (net (code "2") (name "/AVDD") (class "Default")
      (node (ref "C10") (pin "1") (pinfunction "1_1") (pintype "passive"))
      (node (ref "C41") (pin "1") (pinfunction "1_1") (pintype "passive"))
      (node (ref "C6") (pin "1") (pinfunction "1_1") (pintype "passive"))
      (node (ref "C9") (pin "1") (pinfunction "1_1") (pintype "passive"))
      (node (ref "IC1") (pin "62") (pinfunction "AVDD_62") (pintype "power_in"))
      (node (ref "IC13") (pin "5") (pinfunction "VREF_5") (pintype "bidirectional"))
      (node (ref "TP7") (pin "TP") (pinfunction "TP_TP") (pintype "input"))
    )
    (net (code "3") (name "/BASELINE") (class "Default")
      (node (ref "IC1") (pin "56") (pinfunction "BASELINE_56") (pintype "output"))
      (node (ref "TP10") (pin "TP") (pinfunction "TP_TP") (pintype "input"))
    )
    (net (code "4") (name "/CAP_PRECHAR") (class "Default")
      (node (ref "C38") (pin "2") (pinfunction "2_2") (pintype "passive"))
      (node (ref "IC1") (pin "14") (pinfunction "CAP_PRECHARGE_EXT_14") (pintype "input"))
      (node (ref "TP21") (pin "TP") (pinfunction "TP_TP") (pintype "input"))
    )
    (net (code "5") (name "/CAP_PRECHAR_1") (class "Default")
      (node (ref "IC21") (pin "12") (pinfunction "D4_12") (pintype "bidirectional"))
      (node (ref "JP1") (pin "1") (pinfunction "1_1") (pintype "passive"))
    )
    (net (code "6") (name "/CLK") (class "Default")
      (node (ref "IC1") (pin "20") (pinfunction "CLK_20") (pintype "bidirectional"))
      (node (ref "R30") (pin "1") (pinfunction "1_1") (pintype "passive"))
      (node (ref "R31") (pin "2") (pinfunction "2_2") (pintype "passive"))
    )
    (net (code "7") (name "/CLK_ADC") (class "Default")
      (node (ref "IC22") (pin "P$10") (pinfunction "SCLK_P$10") (pintype "bidirectional"))
      (node (ref "J1") (pin "A44") (pinfunction "A44_A44") (pintype "bidirectional"))
      (node (ref "U$5") (pin "P$10") (pinfunction "SCLK_P$10") (pintype "bidirectional"))
    )
    (net (code "8") (name "/CLK_DAC") (class "Default")
      (node (ref "IC23") (pin "10") (pinfunction "SCLK_10") (pintype "bidirectional"))
      (node (ref "J1") (pin "A17") (pinfunction "A17_A17") (pintype "bidirectional"))
    )
    (net (code "9") (name "/CLK_PRECH1") (class "Default")
      (node (ref "IC1") (pin "9") (pinfunction "CLK_PRECH1_9") (pintype "bidirectional"))
      (node (ref "R40") (pin "1") (pinfunction "1_1") (pintype "passive"))
      (node (ref "R41") (pin "2") (pinfunction "2_2") (pintype "passive"))
    )
    (net (code "10") (name "/CLK_PRECH1_T") (class "Default")
      (node (ref "J1") (pin "A39") (pinfunction "A39_A39") (pintype "bidirectional"))
      (node (ref "R40") (pin "2") (pinfunction "2_2") (pintype "passive"))
    )
    (net (code "11") (name "/CLK_PRECH2") (class "Default")
      (node (ref "IC1") (pin "10") (pinfunction "CLK_PRECH2_10") (pintype "bidirectional"))
      (node (ref "R42") (pin "1") (pinfunction "1_1") (pintype "passive"))
      (node (ref "R43") (pin "2") (pinfunction "2_2") (pintype "passive"))
    )
    (net (code "12") (name "/CLK_PRECH2_T") (class "Default")
      (node (ref "J1") (pin "A35") (pinfunction "A35_A35") (pintype "bidirectional"))
      (node (ref "R42") (pin "2") (pinfunction "2_2") (pintype "passive"))
    )
    (net (code "13") (name "/CLK_REF") (class "Default")
      (node (ref "IC18") (pin "4") (pinfunction "CLK_4") (pintype "bidirectional"))
      (node (ref "IC19") (pin "4") (pinfunction "CLK_4") (pintype "bidirectional"))
      (node (ref "IC20") (pin "4") (pinfunction "CLK_4") (pintype "bidirectional"))
      (node (ref "J1") (pin "A9") (pinfunction "A9_A9") (pintype "bidirectional"))
    )
    (net (code "14") (name "/CLK_T") (class "Default")
      (node (ref "J1") (pin "A21") (pinfunction "A21_A21") (pintype "bidirectional"))
      (node (ref "R30") (pin "2") (pinfunction "2_2") (pintype "passive"))
    )
    (net (code "15") (name "/CS_B0") (class "Default")
      (node (ref "IC1") (pin "41") (pinfunction "CS_B0_41") (pintype "bidirectional"))
      (node (ref "R14") (pin "1") (pinfunction "1_1") (pintype "passive"))
      (node (ref "R15") (pin "2") (pinfunction "2_2") (pintype "passive"))
    )
    (net (code "16") (name "/CS_B0_T") (class "Default")
      (node (ref "J1") (pin "A26") (pinfunction "A26_A26") (pintype "bidirectional"))
      (node (ref "R14") (pin "2") (pinfunction "2_2") (pintype "passive"))
    )
    (net (code "17") (name "/CS_B1") (class "Default")
      (node (ref "IC1") (pin "42") (pinfunction "CS_B1_42") (pintype "bidirectional"))
      (node (ref "R16") (pin "1") (pinfunction "1_1") (pintype "passive"))
      (node (ref "R17") (pin "2") (pinfunction "2_2") (pintype "passive"))
    )
    (net (code "18") (name "/CS_B1_T") (class "Default")
      (node (ref "J1") (pin "A28") (pinfunction "A28_A28") (pintype "bidirectional"))
      (node (ref "R16") (pin "2") (pinfunction "2_2") (pintype "passive"))
    )
    (net (code "19") (name "/CS_B2") (class "Default")
      (node (ref "IC1") (pin "43") (pinfunction "CS_B2_43") (pintype "bidirectional"))
      (node (ref "R18") (pin "1") (pinfunction "1_1") (pintype "passive"))
      (node (ref "R19") (pin "2") (pinfunction "2_2") (pintype "passive"))
    )
    (net (code "20") (name "/CS_B2_T") (class "Default")
      (node (ref "J1") (pin "A30") (pinfunction "A30_A30") (pintype "bidirectional"))
      (node (ref "R18") (pin "2") (pinfunction "2_2") (pintype "passive"))
    )
    (net (code "21") (name "/CS_B3") (class "Default")
      (node (ref "IC1") (pin "44") (pinfunction "CS_B3_44") (pintype "bidirectional"))
      (node (ref "R20") (pin "1") (pinfunction "1_1") (pintype "passive"))
      (node (ref "R21") (pin "2") (pinfunction "2_2") (pintype "passive"))
    )
    (net (code "22") (name "/CS_B3_T") (class "Default")
      (node (ref "J1") (pin "A32") (pinfunction "A32_A32") (pintype "bidirectional"))
      (node (ref "R20") (pin "2") (pinfunction "2_2") (pintype "passive"))
    )
    (net (code "23") (name "/CS_B4") (class "Default")
      (node (ref "IC1") (pin "45") (pinfunction "CS_B4_45") (pintype "bidirectional"))
      (node (ref "R22") (pin "1") (pinfunction "1_1") (pintype "passive"))
      (node (ref "R23") (pin "2") (pinfunction "2_2") (pintype "passive"))
    )
    (net (code "24") (name "/CS_B4_T") (class "Default")
      (node (ref "J1") (pin "A36") (pinfunction "A36_A36") (pintype "bidirectional"))
      (node (ref "R22") (pin "2") (pinfunction "2_2") (pintype "passive"))
    )
    (net (code "25") (name "/CS_B5") (class "Default")
      (node (ref "IC1") (pin "46") (pinfunction "CS_B5_46") (pintype "bidirectional"))
      (node (ref "R24") (pin "1") (pinfunction "1_1") (pintype "passive"))
      (node (ref "R25") (pin "2") (pinfunction "2_2") (pintype "passive"))
    )
    (net (code "26") (name "/CS_B5_T") (class "Default")
      (node (ref "J1") (pin "A38") (pinfunction "A38_A38") (pintype "bidirectional"))
      (node (ref "R24") (pin "2") (pinfunction "2_2") (pintype "passive"))
    )
    (net (code "27") (name "/CS_REF_1") (class "Default")
      (node (ref "IC18") (pin "6") (pinfunction "CS~{}_6") (pintype "bidirectional"))
      (node (ref "J1") (pin "A13") (pinfunction "A13_A13") (pintype "bidirectional"))
    )
    (net (code "28") (name "/CS_REF_2") (class "Default")
      (node (ref "IC19") (pin "6") (pinfunction "CS~{}_6") (pintype "bidirectional"))
      (node (ref "J1") (pin "A11") (pinfunction "A11_A11") (pintype "bidirectional"))
    )
    (net (code "29") (name "/CS_REF_3") (class "Default")
      (node (ref "IC20") (pin "6") (pinfunction "CS~{}_6") (pintype "bidirectional"))
      (node (ref "J1") (pin "A8") (pinfunction "A8_A8") (pintype "bidirectional"))
    )
    (net (code "30") (name "/DGND") (class "Default")
      (node (ref "C11") (pin "2") (pinfunction "2_2") (pintype "passive"))
      (node (ref "C12") (pin "2") (pinfunction "2_2") (pintype "passive"))
      (node (ref "C13") (pin "2") (pinfunction "2_2") (pintype "passive"))
      (node (ref "IC1") (pin "28") (pinfunction "DGND_28") (pintype "power_in"))
      (node (ref "IC10") (pin "2") (pinfunction "GND_2") (pintype "bidirectional"))
      (node (ref "R3") (pin "1") (pinfunction "1_1") (pintype "passive"))
      (node (ref "TP29") (pin "TP") (pinfunction "TP_TP") (pintype "input"))
    )
    (net (code "31") (name "/DVDD") (class "Default")
      (node (ref "C11") (pin "1") (pinfunction "1_1") (pintype "passive"))
      (node (ref "C12") (pin "1") (pinfunction "1_1") (pintype "passive"))
      (node (ref "C13") (pin "1") (pinfunction "1_1") (pintype "passive"))
      (node (ref "C40") (pin "1") (pinfunction "1_1") (pintype "passive"))
      (node (ref "IC1") (pin "27") (pinfunction "DVDD_27") (pintype "power_in"))
      (node (ref "IC10") (pin "5") (pinfunction "VREF_5") (pintype "bidirectional"))
      (node (ref "TP8") (pin "TP") (pinfunction "TP_TP") (pintype "input"))
    )
    (net (code "32") (name "/GND") (class "Default")
      (node (ref "C1") (pin "2") (pinfunction "2_2") (pintype "passive"))
      (node (ref "C14") (pin "2") (pinfunction "2_2") (pintype "passive"))
      (node (ref "C15") (pin "2") (pinfunction "2_2") (pintype "passive"))
      (node (ref "C16") (pin "2") (pinfunction "2_2") (pintype "passive"))
      (node (ref "C17") (pin "2") (pinfunction "2_2") (pintype "passive"))
      (node (ref "C18") (pin "2") (pinfunction "2_2") (pintype "passive"))
      (node (ref "C19") (pin "2") (pinfunction "2_2") (pintype "passive"))
      (node (ref "C2") (pin "2") (pinfunction "2_2") (pintype "passive"))
      (node (ref "C20") (pin "2") (pinfunction "2_2") (pintype "passive"))
      (node (ref "C21") (pin "2") (pinfunction "2_2") (pintype "passive"))
      (node (ref "C22") (pin "2") (pinfunction "2_2") (pintype "passive"))
      (node (ref "C23") (pin "2") (pinfunction "2_2") (pintype "passive"))
      (node (ref "C24") (pin "2") (pinfunction "2_2") (pintype "passive"))
      (node (ref "C25") (pin "2") (pinfunction "2_2") (pintype "passive"))
      (node (ref "C26") (pin "2") (pinfunction "2_2") (pintype "passive"))
      (node (ref "C27") (pin "2") (pinfunction "2_2") (pintype "passive"))
      (node (ref "C28") (pin "2") (pinfunction "2_2") (pintype "passive"))
      (node (ref "C29") (pin "2") (pinfunction "2_2") (pintype "passive"))
      (node (ref "C3") (pin "2") (pinfunction "2_2") (pintype "passive"))
      (node (ref "C30") (pin "2") (pinfunction "2_2") (pintype "passive"))
      (node (ref "C31") (pin "2") (pinfunction "2_2") (pintype "passive"))
      (node (ref "C32") (pin "2") (pinfunction "2_2") (pintype "passive"))
      (node (ref "C33") (pin "2") (pinfunction "2_2") (pintype "passive"))
      (node (ref "C34") (pin "2") (pinfunction "2_2") (pintype "passive"))
      (node (ref "C35") (pin "2") (pinfunction "2_2") (pintype "passive"))
      (node (ref "C39") (pin "1") (pinfunction "1_1") (pintype "passive"))
      (node (ref "C4") (pin "2") (pinfunction "2_2") (pintype "passive"))
      (node (ref "C40") (pin "2") (pinfunction "2_2") (pintype "passive"))
      (node (ref "C41") (pin "2") (pinfunction "2_2") (pintype "passive"))
      (node (ref "C42") (pin "2") (pinfunction "2_2") (pintype "passive"))
      (node (ref "C43") (pin "2") (pinfunction "2_2") (pintype "passive"))
      (node (ref "C44") (pin "2") (pinfunction "2_2") (pintype "passive"))
      (node (ref "C45") (pin "2") (pinfunction "2_2") (pintype "passive"))
      (node (ref "C46") (pin "2") (pinfunction "2_2") (pintype "passive"))
      (node (ref "C5") (pin "2") (pinfunction "2_2") (pintype "passive"))
      (node (ref "C7") (pin "2") (pinfunction "2_2") (pintype "passive"))
      (node (ref "C8") (pin "2") (pinfunction "2_2") (pintype "passive"))
      (node (ref "IC11") (pin "2") (pinfunction "GND_2") (pintype "passive"))
      (node (ref "IC12") (pin "4") (pinfunction "V-_4") (pintype "bidirectional"))
      (node (ref "IC14") (pin "4") (pinfunction "V-_4") (pintype "bidirectional"))
      (node (ref "IC16") (pin "2") (pinfunction "GND_2") (pintype "bidirectional"))
      (node (ref "IC17") (pin "2") (pinfunction "GND_2") (pintype "bidirectional"))
      (node (ref "IC18") (pin "3") (pinfunction "GND_3") (pintype "bidirectional"))
      (node (ref "IC18") (pin "8") (pinfunction "A_8") (pintype "bidirectional"))
      (node (ref "IC19") (pin "3") (pinfunction "GND_3") (pintype "bidirectional"))
      (node (ref "IC19") (pin "8") (pinfunction "A_8") (pintype "bidirectional"))
      (node (ref "IC2") (pin "2") (pinfunction "GND_2") (pintype "bidirectional"))
      (node (ref "IC20") (pin "3") (pinfunction "GND_3") (pintype "bidirectional"))
      (node (ref "IC20") (pin "8") (pinfunction "A_8") (pintype "bidirectional"))
      (node (ref "IC21") (pin "10") (pinfunction "S3B_10") (pintype "bidirectional"))
      (node (ref "IC21") (pin "13") (pinfunction "S4B_13") (pintype "bidirectional"))
      (node (ref "IC21") (pin "8") (pinfunction "GND_8") (pintype "bidirectional"))
      (node (ref "IC22") (pin "P$3") (pinfunction "RGND_P$3") (pintype "bidirectional"))
      (node (ref "IC22") (pin "P$6") (pinfunction "GND_P$6") (pintype "bidirectional"))
      (node (ref "IC23") (pin "3") (pinfunction "GND_3") (pintype "bidirectional"))
      (node (ref "IC3") (pin "2") (pinfunction "GND_2") (pintype "bidirectional"))
      (node (ref "IC4") (pin "2") (pinfunction "GND_2") (pintype "bidirectional"))
      (node (ref "IC5") (pin "2") (pinfunction "GND_2") (pintype "bidirectional"))
      (node (ref "IC6") (pin "2") (pinfunction "GND_2") (pintype "bidirectional"))
      (node (ref "IC7") (pin "2") (pinfunction "GND_2") (pintype "bidirectional"))
      (node (ref "IC8") (pin "2") (pinfunction "GND_2") (pintype "bidirectional"))
      (node (ref "IC9") (pin "2") (pinfunction "GND_2") (pintype "passive"))
      (node (ref "J1") (pin "B10") (pinfunction "B10_B10") (pintype "bidirectional"))
      (node (ref "J1") (pin "B11") (pinfunction "B11_B11") (pintype "bidirectional"))
      (node (ref "J1") (pin "B12") (pinfunction "B12_B12") (pintype "bidirectional"))
      (node (ref "J1") (pin "B13") (pinfunction "B13_B13") (pintype "bidirectional"))
      (node (ref "J1") (pin "B14") (pinfunction "B14_B14") (pintype "bidirectional"))
      (node (ref "J1") (pin "B15") (pinfunction "B15_B15") (pintype "bidirectional"))
      (node (ref "J1") (pin "B16") (pinfunction "B16_B16") (pintype "bidirectional"))
      (node (ref "J1") (pin "B17") (pinfunction "B17_B17") (pintype "bidirectional"))
      (node (ref "J1") (pin "B18") (pinfunction "B18_B18") (pintype "bidirectional"))
      (node (ref "J1") (pin "B19") (pinfunction "B19_B19") (pintype "bidirectional"))
      (node (ref "J1") (pin "B2") (pinfunction "B2_B2") (pintype "bidirectional"))
      (node (ref "J1") (pin "B20") (pinfunction "B20_B20") (pintype "bidirectional"))
      (node (ref "J1") (pin "B21") (pinfunction "B21_B21") (pintype "bidirectional"))
      (node (ref "J1") (pin "B22") (pinfunction "B22_B22") (pintype "bidirectional"))
      (node (ref "J1") (pin "B23") (pinfunction "B23_B23") (pintype "bidirectional"))
      (node (ref "J1") (pin "B24") (pinfunction "B24_B24") (pintype "bidirectional"))
      (node (ref "J1") (pin "B25") (pinfunction "B25_B25") (pintype "bidirectional"))
      (node (ref "J1") (pin "B26") (pinfunction "B26_B26") (pintype "bidirectional"))
      (node (ref "J1") (pin "B27") (pinfunction "B27_B27") (pintype "bidirectional"))
      (node (ref "J1") (pin "B28") (pinfunction "B28_B28") (pintype "bidirectional"))
      (node (ref "J1") (pin "B29") (pinfunction "B29_B29") (pintype "bidirectional"))
      (node (ref "J1") (pin "B30") (pinfunction "B30_B30") (pintype "bidirectional"))
      (node (ref "J1") (pin "B31") (pinfunction "B31_B31") (pintype "bidirectional"))
      (node (ref "J1") (pin "B32") (pinfunction "B32_B32") (pintype "bidirectional"))
      (node (ref "J1") (pin "B33") (pinfunction "B33_B33") (pintype "bidirectional"))
      (node (ref "J1") (pin "B34") (pinfunction "B34_B34") (pintype "bidirectional"))
      (node (ref "J1") (pin "B35") (pinfunction "B35_B35") (pintype "bidirectional"))
      (node (ref "J1") (pin "B36") (pinfunction "B36_B36") (pintype "bidirectional"))
      (node (ref "J1") (pin "B37") (pinfunction "B37_B37") (pintype "bidirectional"))
      (node (ref "J1") (pin "B38") (pinfunction "B38_B38") (pintype "bidirectional"))
      (node (ref "J1") (pin "B39") (pinfunction "B39_B39") (pintype "bidirectional"))
      (node (ref "J1") (pin "B40") (pinfunction "B40_B40") (pintype "bidirectional"))
      (node (ref "J1") (pin "B41") (pinfunction "B41_B41") (pintype "bidirectional"))
      (node (ref "J1") (pin "B42") (pinfunction "B42_B42") (pintype "bidirectional"))
      (node (ref "J1") (pin "B43") (pinfunction "B43_B43") (pintype "bidirectional"))
      (node (ref "J1") (pin "B44") (pinfunction "B44_B44") (pintype "bidirectional"))
      (node (ref "J1") (pin "B45") (pinfunction "B45_B45") (pintype "bidirectional"))
      (node (ref "J1") (pin "B47") (pinfunction "B47_B47") (pintype "bidirectional"))
      (node (ref "J1") (pin "B5") (pinfunction "B5_B5") (pintype "bidirectional"))
      (node (ref "J1") (pin "B6") (pinfunction "B6_B6") (pintype "bidirectional"))
      (node (ref "J1") (pin "B7") (pinfunction "B7_B7") (pintype "bidirectional"))
      (node (ref "J1") (pin "B8") (pinfunction "B8_B8") (pintype "bidirectional"))
      (node (ref "J1") (pin "B9") (pinfunction "B9_B9") (pintype "bidirectional"))
      (node (ref "JP3") (pin "1") (pinfunction "1_1") (pintype "passive"))
      (node (ref "R15") (pin "1") (pinfunction "1_1") (pintype "passive"))
      (node (ref "R17") (pin "1") (pinfunction "1_1") (pintype "passive"))
      (node (ref "R19") (pin "1") (pinfunction "1_1") (pintype "passive"))
      (node (ref "R2") (pin "3") (pinfunction "3_3") (pintype "passive"))
      (node (ref "R21") (pin "1") (pinfunction "1_1") (pintype "passive"))
      (node (ref "R23") (pin "1") (pinfunction "1_1") (pintype "passive"))
      (node (ref "R25") (pin "1") (pinfunction "1_1") (pintype "passive"))
      (node (ref "R27") (pin "1") (pinfunction "1_1") (pintype "passive"))
      (node (ref "R29") (pin "1") (pinfunction "1_1") (pintype "passive"))
      (node (ref "R31") (pin "1") (pinfunction "1_1") (pintype "passive"))
      (node (ref "R33") (pin "1") (pinfunction "1_1") (pintype "passive"))
      (node (ref "R35") (pin "1") (pinfunction "1_1") (pintype "passive"))
      (node (ref "R37") (pin "1") (pinfunction "1_1") (pintype "passive"))
      (node (ref "R39") (pin "1") (pinfunction "1_1") (pintype "passive"))
      (node (ref "R4") (pin "3") (pinfunction "3_3") (pintype "passive"))
      (node (ref "R41") (pin "1") (pinfunction "1_1") (pintype "passive"))
      (node (ref "R43") (pin "1") (pinfunction "1_1") (pintype "passive"))
      (node (ref "R5") (pin "3") (pinfunction "3_3") (pintype "passive"))
      (node (ref "R6") (pin "3") (pinfunction "3_3") (pintype "passive"))
      (node (ref "R7") (pin "1") (pinfunction "1_1") (pintype "passive"))
      (node (ref "R8") (pin "1") (pinfunction "1_1") (pintype "passive"))
      (node (ref "R9") (pin "1") (pinfunction "1_1") (pintype "passive"))
      (node (ref "TP18") (pin "TP") (pinfunction "TP_TP") (pintype "input"))
      (node (ref "U$5") (pin "P$3") (pinfunction "RGND_P$3") (pintype "bidirectional"))
      (node (ref "U$5") (pin "P$6") (pinfunction "GND_P$6") (pintype "bidirectional"))
    )
    (net (code "33") (name "/HOLD") (class "Default")
      (node (ref "IC1") (pin "37") (pinfunction "HOLD_37") (pintype "bidirectional"))
      (node (ref "R38") (pin "1") (pinfunction "1_1") (pintype "passive"))
      (node (ref "R39") (pin "2") (pinfunction "2_2") (pintype "passive"))
    )
    (net (code "34") (name "/HOLD_T") (class "Default")
      (node (ref "J1") (pin "A24") (pinfunction "A24_A24") (pintype "bidirectional"))
      (node (ref "R38") (pin "2") (pinfunction "2_2") (pintype "passive"))
    )
    (net (code "35") (name "/MUX_DAC_EN") (class "Default")
      (node (ref "IC21") (pin "15") (pinfunction "~{EN}_15") (pintype "bidirectional"))
      (node (ref "J1") (pin "A20") (pinfunction "A20_A20") (pintype "bidirectional"))
    )
    (net (code "36") (name "/MUX_DAC_SEL") (class "Default")
      (node (ref "IC21") (pin "1") (pinfunction "IN_1") (pintype "bidirectional"))
      (node (ref "J1") (pin "A19") (pinfunction "A19_A19") (pintype "bidirectional"))
    )
    (net (code "37") (name "/MUX_REF_1") (class "Default")
      (node (ref "IC2") (pin "6") (pinfunction "IN_6") (pintype "bidirectional"))
      (node (ref "J1") (pin "A12") (pinfunction "A12_A12") (pintype "bidirectional"))
    )
    (net (code "38") (name "/MUX_REF_2") (class "Default")
      (node (ref "IC3") (pin "6") (pinfunction "IN_6") (pintype "bidirectional"))
      (node (ref "J1") (pin "A10") (pinfunction "A10_A10") (pintype "bidirectional"))
    )
    (net (code "39") (name "/MUX_REF_3") (class "Default")
      (node (ref "IC4") (pin "6") (pinfunction "IN_6") (pintype "bidirectional"))
      (node (ref "J1") (pin "A6") (pinfunction "A6_A6") (pintype "bidirectional"))
    )
    (net (code "40") (name "/OP_MODE") (class "Default")
      (node (ref "IC1") (pin "11") (pinfunction "OP_MODE_11") (pintype "bidirectional"))
      (node (ref "R26") (pin "1") (pinfunction "1_1") (pintype "passive"))
      (node (ref "R27") (pin "2") (pinfunction "2_2") (pintype "passive"))
    )
    (net (code "41") (name "/OP_MODE_T") (class "Default")
      (node (ref "J1") (pin "A34") (pinfunction "A34_A34") (pintype "bidirectional"))
      (node (ref "R26") (pin "2") (pinfunction "2_2") (pintype "passive"))
    )
    (net (code "42") (name "/OUT_S") (class "Default")
      (node (ref "IC1") (pin "35") (pinfunction "OUT_S_35") (pintype "bidirectional"))
      (node (ref "R32") (pin "1") (pinfunction "1_1") (pintype "passive"))
      (node (ref "R33") (pin "2") (pinfunction "2_2") (pintype "passive"))
    )
    (net (code "43") (name "/OUT_S_T") (class "Default")
      (node (ref "J1") (pin "A22") (pinfunction "A22_A22") (pintype "bidirectional"))
      (node (ref "R32") (pin "2") (pinfunction "2_2") (pintype "passive"))
    )
    (net (code "44") (name "/POT_R1") (class "Default")
      (node (ref "JP4") (pin "3") (pinfunction "3_3") (pintype "passive"))
      (node (ref "R1") (pin "2") (pinfunction "2_2") (pintype "passive"))
      (node (ref "R1") (pin "3") (pinfunction "3_3") (pintype "passive"))
      (node (ref "TP27") (pin "TP") (pinfunction "TP_TP") (pintype "input"))
    )
    (net (code "45") (name "/POT_R2") (class "Default")
      (node (ref "JP4") (pin "1") (pinfunction "1_1") (pintype "passive"))
      (node (ref "R2") (pin "1") (pinfunction "1_1") (pintype "passive"))
      (node (ref "R2") (pin "2") (pinfunction "2_2") (pintype "passive"))
      (node (ref "TP28") (pin "TP") (pinfunction "TP_TP") (pintype "input"))
    )
    (net (code "46") (name "/POT_R4") (class "Default")
      (node (ref "IC2") (pin "3") (pinfunction "A1_3") (pintype "bidirectional"))
      (node (ref "R4") (pin "2") (pinfunction "2_2") (pintype "passive"))
      (node (ref "TP24") (pin "TP") (pinfunction "TP_TP") (pintype "input"))
    )
    (net (code "47") (name "/POT_R5") (class "Default")
      (node (ref "IC3") (pin "3") (pinfunction "A1_3") (pintype "bidirectional"))
      (node (ref "R5") (pin "2") (pinfunction "2_2") (pintype "passive"))
      (node (ref "TP25") (pin "TP") (pinfunction "TP_TP") (pintype "input"))
    )
    (net (code "48") (name "/POT_R6") (class "Default")
      (node (ref "IC4") (pin "3") (pinfunction "A1_3") (pintype "bidirectional"))
      (node (ref "R6") (pin "2") (pinfunction "2_2") (pintype "passive"))
      (node (ref "TP26") (pin "TP") (pinfunction "TP_TP") (pintype "input"))
    )
    (net (code "49") (name "/REFIN_DAC") (class "Default")
      (node (ref "C28") (pin "1") (pinfunction "1_1") (pintype "passive"))
      (node (ref "IC23") (pin "6") (pinfunction "REFIN_6") (pintype "bidirectional"))
      (node (ref "IC8") (pin "5") (pinfunction "VREF_5") (pintype "bidirectional"))
      (node (ref "TP15") (pin "TP") (pinfunction "TP_TP") (pintype "input"))
    )
    (net (code "50") (name "/REF_ADC") (class "Default")
      (node (ref "C17") (pin "1") (pinfunction "1_1") (pintype "passive"))
      (node (ref "C18") (pin "1") (pinfunction "1_1") (pintype "passive"))
      (node (ref "C23") (pin "1") (pinfunction "1_1") (pintype "passive"))
      (node (ref "C24") (pin "1") (pinfunction "1_1") (pintype "passive"))
      (node (ref "C31") (pin "1") (pinfunction "1_1") (pintype "passive"))
      (node (ref "IC17") (pin "5") (pinfunction "VREF_5") (pintype "bidirectional"))
      (node (ref "IC22") (pin "P$2") (pinfunction "REF_P$2") (pintype "bidirectional"))
      (node (ref "TP17") (pin "TP") (pinfunction "TP_TP") (pintype "input"))
      (node (ref "U$5") (pin "P$2") (pinfunction "REF_P$2") (pintype "bidirectional"))
    )
    (net (code "51") (name "/RES_BIAS_EXT") (class "Default")
      (node (ref "IC1") (pin "6") (pinfunction "RES_BIAS_EXT_6") (pintype "bidirectional"))
      (node (ref "JP4") (pin "2") (pinfunction "2_2") (pintype "passive"))
    )
    (net (code "52") (name "/RST") (class "Default")
      (node (ref "IC1") (pin "38") (pinfunction "RST_38") (pintype "bidirectional"))
      (node (ref "R36") (pin "1") (pinfunction "1_1") (pintype "passive"))
      (node (ref "R37") (pin "2") (pinfunction "2_2") (pintype "passive"))
    )
    (net (code "53") (name "/RST_CSA") (class "Default")
      (node (ref "IC1") (pin "12") (pinfunction "RST_CSA_12") (pintype "bidirectional"))
      (node (ref "R28") (pin "1") (pinfunction "1_1") (pintype "passive"))
      (node (ref "R29") (pin "2") (pinfunction "2_2") (pintype "passive"))
    )
    (net (code "54") (name "/RST_CSA_T") (class "Default")
      (node (ref "J1") (pin "A25") (pinfunction "A25_A25") (pintype "bidirectional"))
      (node (ref "R28") (pin "2") (pinfunction "2_2") (pintype "passive"))
    )
    (net (code "55") (name "/RST_T") (class "Default")
      (node (ref "J1") (pin "A27") (pinfunction "A27_A27") (pintype "bidirectional"))
      (node (ref "R36") (pin "2") (pinfunction "2_2") (pintype "passive"))
    )
    (net (code "56") (name "/SDI_DAC") (class "Default")
      (node (ref "IC23") (pin "9") (pinfunction "DIN_9") (pintype "bidirectional"))
      (node (ref "J1") (pin "A15") (pinfunction "A15_A15") (pintype "bidirectional"))
    )
    (net (code "57") (name "/SDI_REF") (class "Default")
      (node (ref "IC18") (pin "5") (pinfunction "SDI_5") (pintype "bidirectional"))
      (node (ref "IC19") (pin "5") (pinfunction "SDI_5") (pintype "bidirectional"))
      (node (ref "IC20") (pin "5") (pinfunction "SDI_5") (pintype "bidirectional"))
      (node (ref "J1") (pin "A7") (pinfunction "A7_A7") (pintype "bidirectional"))
    )
    (net (code "58") (name "/SDO_ADC1") (class "Default")
      (node (ref "IC22") (pin "P$8") (pinfunction "DOUT_P$8") (pintype "bidirectional"))
      (node (ref "J1") (pin "A40") (pinfunction "A40_A40") (pintype "bidirectional"))
    )
    (net (code "59") (name "/SDO_ADC2") (class "Default")
      (node (ref "J1") (pin "A16") (pinfunction "A16_A16") (pintype "bidirectional"))
      (node (ref "U$5") (pin "P$8") (pinfunction "DOUT_P$8") (pintype "bidirectional"))
    )
    (net (code "60") (name "/SGN") (class "Default")
      (node (ref "IC1") (pin "39") (pinfunction "SGN_39") (pintype "bidirectional"))
      (node (ref "R34") (pin "1") (pinfunction "1_1") (pintype "passive"))
      (node (ref "R35") (pin "2") (pinfunction "2_2") (pintype "passive"))
    )
    (net (code "61") (name "/SGN_T") (class "Default")
      (node (ref "J1") (pin "A31") (pinfunction "A31_A31") (pintype "bidirectional"))
      (node (ref "R34") (pin "2") (pinfunction "2_2") (pintype "passive"))
    )
    (net (code "62") (name "/V0NDAC") (class "Default")
      (node (ref "IC21") (pin "5") (pinfunction "S2A_5") (pintype "bidirectional"))
      (node (ref "IC23") (pin "2") (pinfunction "VOUTB_2") (pintype "bidirectional"))
    )
    (net (code "63") (name "/V0PDAC") (class "Default")
      (node (ref "IC21") (pin "2") (pinfunction "S1A_2") (pintype "bidirectional"))
      (node (ref "IC23") (pin "1") (pinfunction "VOUTA_1") (pintype "bidirectional"))
    )
    (net (code "64") (name "/V1NDAC") (class "Default")
      (node (ref "IC21") (pin "14") (pinfunction "S4A_14") (pintype "bidirectional"))
      (node (ref "IC23") (pin "5") (pinfunction "VOUTD_5") (pintype "bidirectional"))
    )
    (net (code "65") (name "/V1PDAC") (class "Default")
      (node (ref "IC21") (pin "11") (pinfunction "S3A_11") (pintype "bidirectional"))
      (node (ref "IC23") (pin "4") (pinfunction "VOUTC_4") (pintype "bidirectional"))
    )
    (net (code "66") (name "/VDD") (class "Default")
      (node (ref "C1") (pin "1") (pinfunction "1_1") (pintype "passive"))
      (node (ref "C15") (pin "1") (pinfunction "1_1") (pintype "passive"))
      (node (ref "C16") (pin "1") (pinfunction "1_1") (pintype "passive"))
      (node (ref "C19") (pin "1") (pinfunction "1_1") (pintype "passive"))
      (node (ref "C2") (pin "1") (pinfunction "1_1") (pintype "passive"))
      (node (ref "C20") (pin "1") (pinfunction "1_1") (pintype "passive"))
      (node (ref "C25") (pin "1") (pinfunction "1_1") (pintype "passive"))
      (node (ref "C3") (pin "1") (pinfunction "1_1") (pintype "passive"))
      (node (ref "C30") (pin "1") (pinfunction "1_1") (pintype "passive"))
      (node (ref "C39") (pin "2") (pinfunction "2_2") (pintype "passive"))
      (node (ref "C4") (pin "1") (pinfunction "1_1") (pintype "passive"))
      (node (ref "C44") (pin "1") (pinfunction "1_1") (pintype "passive"))
      (node (ref "IC11") (pin "3") (pinfunction "VO_3") (pintype "passive"))
      (node (ref "IC16") (pin "3") (pinfunction "EN_3") (pintype "bidirectional"))
      (node (ref "IC16") (pin "4") (pinfunction "VIN_4") (pintype "bidirectional"))
      (node (ref "IC17") (pin "3") (pinfunction "EN_3") (pintype "bidirectional"))
      (node (ref "IC17") (pin "4") (pinfunction "VIN_4") (pintype "bidirectional"))
      (node (ref "IC18") (pin "2") (pinfunction "VDD_2") (pintype "bidirectional"))
      (node (ref "IC19") (pin "2") (pinfunction "VDD_2") (pintype "bidirectional"))
      (node (ref "IC2") (pin "5") (pinfunction "VCC_5") (pintype "bidirectional"))
      (node (ref "IC20") (pin "2") (pinfunction "VDD_2") (pintype "bidirectional"))
      (node (ref "IC21") (pin "16") (pinfunction "VDD_16") (pintype "bidirectional"))
      (node (ref "IC22") (pin "P$4") (pinfunction "VDD_P$4") (pintype "bidirectional"))
      (node (ref "IC23") (pin "8") (pinfunction "VDD_8") (pintype "bidirectional"))
      (node (ref "IC3") (pin "5") (pinfunction "VCC_5") (pintype "bidirectional"))
      (node (ref "IC4") (pin "5") (pinfunction "VCC_5") (pintype "bidirectional"))
      (node (ref "IC5") (pin "3") (pinfunction "EN_3") (pintype "bidirectional"))
      (node (ref "IC5") (pin "4") (pinfunction "VIN_4") (pintype "bidirectional"))
      (node (ref "IC6") (pin "3") (pinfunction "EN_3") (pintype "bidirectional"))
      (node (ref "IC6") (pin "4") (pinfunction "VIN_4") (pintype "bidirectional"))
      (node (ref "IC7") (pin "3") (pinfunction "EN_3") (pintype "bidirectional"))
      (node (ref "IC7") (pin "4") (pinfunction "VIN_4") (pintype "bidirectional"))
      (node (ref "IC8") (pin "3") (pinfunction "EN_3") (pintype "bidirectional"))
      (node (ref "IC8") (pin "4") (pinfunction "VIN_4") (pintype "bidirectional"))
      (node (ref "R1") (pin "1") (pinfunction "1_1") (pintype "passive"))
      (node (ref "TP5") (pin "TP") (pinfunction "TP_TP") (pintype "input"))
      (node (ref "U$5") (pin "P$4") (pinfunction "VDD_P$4") (pintype "bidirectional"))
    )
    (net (code "67") (name "/VDD2") (class "Default")
      (node (ref "C46") (pin "1") (pinfunction "1_1") (pintype "passive"))
      (node (ref "C5") (pin "1") (pinfunction "1_1") (pintype "passive"))
      (node (ref "C7") (pin "1") (pinfunction "1_1") (pintype "passive"))
      (node (ref "IC10") (pin "3") (pinfunction "EN_3") (pintype "bidirectional"))
      (node (ref "IC10") (pin "4") (pinfunction "VIN_4") (pintype "bidirectional"))
      (node (ref "IC13") (pin "3") (pinfunction "EN_3") (pintype "bidirectional"))
      (node (ref "IC13") (pin "4") (pinfunction "VIN_4") (pintype "bidirectional"))
      (node (ref "IC9") (pin "3") (pinfunction "VO_3") (pintype "passive"))
      (node (ref "TP6") (pin "TP") (pinfunction "TP_TP") (pintype "input"))
    )
    (net (code "68") (name "/VDD_REF_1") (class "Default")
      (node (ref "C26") (pin "1") (pinfunction "1_1") (pintype "passive"))
      (node (ref "IC18") (pin "7") (pinfunction "B_7") (pintype "bidirectional"))
      (node (ref "IC5") (pin "5") (pinfunction "VREF_5") (pintype "bidirectional"))
      (node (ref "R4") (pin "1") (pinfunction "1_1") (pintype "passive"))
    )
    (net (code "69") (name "/VDD_REF_2") (class "Default")
      (node (ref "C27") (pin "1") (pinfunction "1_1") (pintype "passive"))
      (node (ref "IC19") (pin "7") (pinfunction "B_7") (pintype "bidirectional"))
      (node (ref "IC6") (pin "5") (pinfunction "VREF_5") (pintype "bidirectional"))
      (node (ref "R5") (pin "1") (pinfunction "1_1") (pintype "passive"))
    )
    (net (code "70") (name "/VDD_REF_3") (class "Default")
      (node (ref "C35") (pin "1") (pinfunction "1_1") (pintype "passive"))
      (node (ref "IC20") (pin "7") (pinfunction "B_7") (pintype "bidirectional"))
      (node (ref "IC7") (pin "5") (pinfunction "VREF_5") (pintype "bidirectional"))
      (node (ref "R6") (pin "1") (pinfunction "1_1") (pintype "passive"))
    )
    (net (code "71") (name "/VDD_SUPPLY_1") (class "Default")
      (node (ref "C43") (pin "1") (pinfunction "1_1") (pintype "passive"))
      (node (ref "IC11") (pin "1") (pinfunction "VI_1") (pintype "input"))
      (node (ref "JP5") (pin "1") (pinfunction "1_1") (pintype "passive"))
      (node (ref "TP1") (pin "TP") (pinfunction "TP_TP") (pintype "input"))
    )
    (net (code "72") (name "/VDD_SUPPLY_2") (class "Default")
      (node (ref "C45") (pin "1") (pinfunction "1_1") (pintype "passive"))
      (node (ref "IC9") (pin "1") (pinfunction "VI_1") (pintype "input"))
      (node (ref "JP8") (pin "1") (pinfunction "1_1") (pintype "passive"))
      (node (ref "TP3") (pin "TP") (pinfunction "TP_TP") (pintype "input"))
    )
    (net (code "73") (name "/VDD_SUPPLY_IN_1") (class "Default")
      (node (ref "IC12") (pin "8") (pinfunction "V+_8") (pintype "bidirectional"))
      (node (ref "IC14") (pin "8") (pinfunction "V+_8") (pintype "bidirectional"))
      (node (ref "JP3") (pin "3") (pinfunction "3_3") (pintype "passive"))
      (node (ref "JP5") (pin "2") (pinfunction "2_2") (pintype "passive"))
      (node (ref "TP2") (pin "TP") (pinfunction "TP_TP") (pintype "input"))
    )
    (net (code "74") (name "/VDD_SUPPLY_IN_2") (class "Default")
      (node (ref "JP3") (pin "2") (pinfunction "2_2") (pintype "passive"))
      (node (ref "JP8") (pin "2") (pinfunction "2_2") (pintype "passive"))
      (node (ref "TP4") (pin "TP") (pinfunction "TP_TP") (pintype "input"))
    )
    (net (code "75") (name "/VI+_FIL") (class "Default")
      (node (ref "IC1") (pin "22") (pinfunction "VI+_FIL_22") (pintype "input"))
      (node (ref "JP11") (pin "2") (pinfunction "2_2") (pintype "passive"))
    )
    (net (code "76") (name "/VI+_FIL_DAC") (class "Default")
      (node (ref "IC21") (pin "4") (pinfunction "D1_4") (pintype "bidirectional"))
      (node (ref "JP11") (pin "1") (pinfunction "1_1") (pintype "passive"))
    )
    (net (code "77") (name "/VI-_FIL") (class "Default")
      (node (ref "IC1") (pin "23") (pinfunction "VI-_FIL_23") (pintype "input"))
      (node (ref "JP12") (pin "2") (pinfunction "2_2") (pintype "passive"))
    )
    (net (code "78") (name "/VI-_FIL_DAC") (class "Default")
      (node (ref "IC21") (pin "7") (pinfunction "D2_7") (pintype "bidirectional"))
      (node (ref "JP12") (pin "1") (pinfunction "1_1") (pintype "passive"))
    )
    (net (code "79") (name "/VICM") (class "Default")
      (node (ref "C32") (pin "1") (pinfunction "1_1") (pintype "passive"))
      (node (ref "IC1") (pin "40") (pinfunction "VICM_40") (pintype "input"))
      (node (ref "IC21") (pin "3") (pinfunction "S1B_3") (pintype "bidirectional"))
      (node (ref "IC21") (pin "6") (pinfunction "S2B_6") (pintype "bidirectional"))
      (node (ref "R10") (pin "1") (pinfunction "1_1") (pintype "passive"))
      (node (ref "TP12") (pin "TP") (pinfunction "TP_TP") (pintype "input"))
    )
    (net (code "80") (name "/VICM_BUFF") (class "Default")
      (node (ref "IC12") (pin "1") (pinfunction "OUTA_1") (pintype "bidirectional"))
      (node (ref "IC12") (pin "2") (pinfunction "-INA_2") (pintype "bidirectional"))
      (node (ref "R10") (pin "2") (pinfunction "2_2") (pintype "passive"))
    )
    (net (code "81") (name "/VICM_MUX") (class "Default")
      (node (ref "IC12") (pin "3") (pinfunction "+INA_3") (pintype "bidirectional"))
      (node (ref "IC3") (pin "4") (pinfunction "B_4") (pintype "bidirectional"))
      (node (ref "TP11") (pin "TP") (pinfunction "TP_TP") (pintype "input"))
    )
    (net (code "82") (name "/VIN_CSA") (class "Default")
      (node (ref "IC1") (pin "15") (pinfunction "VIN_CSA_15") (pintype "input"))
      (node (ref "JP1") (pin "3") (pinfunction "3_3") (pintype "passive"))
      (node (ref "JP10") (pin "2") (pinfunction "2_2") (pintype "passive"))
      (node (ref "TP20") (pin "TP") (pinfunction "TP_TP") (pintype "input"))
    )
    (net (code "83") (name "/VIN_CSA_1") (class "Default")
      (node (ref "C36") (pin "1") (pinfunction "1_1") (pintype "passive"))
      (node (ref "IC21") (pin "9") (pinfunction "D3_9") (pintype "bidirectional"))
      (node (ref "JP9") (pin "1") (pinfunction "1_1") (pintype "passive"))
    )
    (net (code "84") (name "/VL_ADC") (class "Default")
      (node (ref "C14") (pin "1") (pinfunction "1_1") (pintype "passive"))
      (node (ref "C21") (pin "1") (pinfunction "1_1") (pintype "passive"))
      (node (ref "C22") (pin "1") (pinfunction "1_1") (pintype "passive"))
      (node (ref "C29") (pin "1") (pinfunction "1_1") (pintype "passive"))
      (node (ref "C8") (pin "1") (pinfunction "1_1") (pintype "passive"))
      (node (ref "IC16") (pin "5") (pinfunction "VREF_5") (pintype "bidirectional"))
      (node (ref "IC22") (pin "P$7") (pinfunction "VL_P$7") (pintype "bidirectional"))
      (node (ref "TP16") (pin "TP") (pinfunction "TP_TP") (pintype "input"))
      (node (ref "U$5") (pin "P$7") (pinfunction "VL_P$7") (pintype "bidirectional"))
    )
    (net (code "85") (name "/VO+_BP_FIL") (class "Default")
      (node (ref "IC1") (pin "24") (pinfunction "VO+_BP_FIL_24") (pintype "output"))
      (node (ref "JP13") (pin "1") (pinfunction "1_1") (pintype "passive"))
    )
    (net (code "86") (name "/VO+_BP_FIL_TEST") (class "Default")
      (node (ref "JP13") (pin "2") (pinfunction "2_2") (pintype "passive"))
      (node (ref "TP22") (pin "TP") (pinfunction "TP_TP") (pintype "input"))
    )
    (net (code "87") (name "/VO+_CH") (class "Default")
      (node (ref "IC1") (pin "50") (pinfunction "VO+_CH_50") (pintype "input"))
      (node (ref "IC22") (pin "P$12") (pinfunction "AIN+_P$12") (pintype "bidirectional"))
    )
    (net (code "88") (name "/VO+_FIL") (class "Default")
      (node (ref "IC1") (pin "30") (pinfunction "VO+_FIL_30") (pintype "output"))
      (node (ref "U$5") (pin "P$12") (pinfunction "AIN+_P$12") (pintype "bidirectional"))
    )
    (net (code "89") (name "/VO-_BP_FIL") (class "Default")
      (node (ref "IC1") (pin "25") (pinfunction "VO-_BP_FIL_25") (pintype "output"))
      (node (ref "JP14") (pin "1") (pinfunction "1_1") (pintype "passive"))
    )
    (net (code "90") (name "/VO-_BP_FIL_TEST") (class "Default")
      (node (ref "JP14") (pin "2") (pinfunction "2_2") (pintype "passive"))
      (node (ref "TP23") (pin "TP") (pinfunction "TP_TP") (pintype "input"))
    )
    (net (code "91") (name "/VO-_CH") (class "Default")
      (node (ref "IC1") (pin "52") (pinfunction "VO-_CH_52") (pintype "input"))
      (node (ref "IC22") (pin "P$1") (pinfunction "AIN-_P$1") (pintype "bidirectional"))
    )
    (net (code "92") (name "/VO-_FIL") (class "Default")
      (node (ref "IC1") (pin "31") (pinfunction "VO-_FIL_31") (pintype "output"))
      (node (ref "U$5") (pin "P$1") (pinfunction "AIN-_P$1") (pintype "bidirectional"))
    )
    (net (code "93") (name "/VOCM") (class "Default")
      (node (ref "C33") (pin "1") (pinfunction "1_1") (pintype "passive"))
      (node (ref "IC1") (pin "34") (pinfunction "VOCM_AUX_34") (pintype "input"))
      (node (ref "IC1") (pin "36") (pinfunction "VOCM_36") (pintype "input"))
      (node (ref "R11") (pin "1") (pinfunction "1_1") (pintype "passive"))
      (node (ref "TP14") (pin "TP") (pinfunction "TP_TP") (pintype "input"))
    )
    (net (code "94") (name "/VOCM_1") (class "Default")
      (node (ref "IC14") (pin "3") (pinfunction "+INA_3") (pintype "bidirectional"))
      (node (ref "IC2") (pin "4") (pinfunction "B_4") (pintype "bidirectional"))
      (node (ref "TP30") (pin "TP") (pinfunction "TP_TP") (pintype "input"))
    )
    (net (code "95") (name "/VOCM_BUFF") (class "Default")
      (node (ref "IC12") (pin "6") (pinfunction "-INB_6") (pintype "bidirectional"))
      (node (ref "IC12") (pin "7") (pinfunction "OUTB_7") (pintype "bidirectional"))
      (node (ref "R11") (pin "2") (pinfunction "2_2") (pintype "passive"))
    )
    (net (code "96") (name "/VOCM_MUX") (class "Default")
      (node (ref "IC12") (pin "5") (pinfunction "+INB_5") (pintype "bidirectional"))
      (node (ref "IC4") (pin "4") (pinfunction "B_4") (pintype "bidirectional"))
      (node (ref "TP13") (pin "TP") (pinfunction "TP_TP") (pintype "input"))
    )
    (net (code "97") (name "/VOUT_CSA") (class "Default")
      (node (ref "IC1") (pin "54") (pinfunction "VOUT_CSA_54") (pintype "output"))
      (node (ref "TP9") (pin "TP") (pinfunction "TP_TP") (pintype "input"))
    )
    (net (code "98") (name "/V_REF_PRECHAR") (class "Default")
      (node (ref "C34") (pin "1") (pinfunction "1_1") (pintype "passive"))
      (node (ref "IC1") (pin "7") (pinfunction "V_REF_PRECHAR_7") (pintype "input"))
      (node (ref "R12") (pin "1") (pinfunction "1_1") (pintype "passive"))
    )
    (net (code "99") (name "/V_REF_PRECHAR_BUFF") (class "Default")
      (node (ref "IC14") (pin "1") (pinfunction "OUTA_1") (pintype "bidirectional"))
      (node (ref "IC14") (pin "2") (pinfunction "-INA_2") (pintype "bidirectional"))
      (node (ref "R12") (pin "2") (pinfunction "2_2") (pintype "passive"))
    )
    (net (code "100") (name "/~{CS_ADC1}") (class "Default")
      (node (ref "IC22") (pin "P$9") (pinfunction "CNVST_P$9") (pintype "bidirectional"))
      (node (ref "J1") (pin "A42") (pinfunction "A42_A42") (pintype "bidirectional"))
    )
    (net (code "101") (name "/~{CS_ADC2}") (class "Default")
      (node (ref "J1") (pin "A18") (pinfunction "A18_A18") (pintype "bidirectional"))
      (node (ref "U$5") (pin "P$9") (pinfunction "CNVST_P$9") (pintype "bidirectional"))
    )
    (net (code "102") (name "/~{CS_DAC}") (class "Default")
      (node (ref "IC23") (pin "7") (pinfunction "~{SYNC}_7") (pintype "bidirectional"))
      (node (ref "J1") (pin "A14") (pinfunction "A14_A14") (pintype "bidirectional"))
    )
    (net (code "103") (name "Net-(C36-Pad2)") (class "Default")
      (node (ref "C36") (pin "2") (pinfunction "2_2") (pintype "passive"))
      (node (ref "C37") (pin "1") (pinfunction "1_1") (pintype "passive"))
      (node (ref "JP9") (pin "2") (pinfunction "2_2") (pintype "passive"))
    )
    (net (code "104") (name "Net-(C37-Pad2)") (class "Default")
      (node (ref "C37") (pin "2") (pinfunction "2_2") (pintype "passive"))
      (node (ref "JP10") (pin "1") (pinfunction "1_1") (pintype "passive"))
    )
    (net (code "105") (name "Net-(C38-Pad1)") (class "Default")
      (node (ref "C38") (pin "1") (pinfunction "1_1") (pintype "passive"))
      (node (ref "JP1") (pin "2") (pinfunction "2_2") (pintype "passive"))
    )
    (net (code "106") (name "Net-(C42-Pad1)") (class "Default")
      (node (ref "C42") (pin "1") (pinfunction "1_1") (pintype "passive"))
      (node (ref "J1") (pin "B50") (pinfunction "B50_B50") (pintype "bidirectional"))
      (node (ref "R8") (pin "2") (pinfunction "2_2") (pintype "passive"))
    )
    (net (code "107") (name "Net-(IC18-W)") (class "Default")
      (node (ref "IC18") (pin "1") (pinfunction "W_1") (pintype "bidirectional"))
      (node (ref "IC2") (pin "1") (pinfunction "A0_1") (pintype "bidirectional"))
    )
    (net (code "108") (name "Net-(IC19-W)") (class "Default")
      (node (ref "IC19") (pin "1") (pinfunction "W_1") (pintype "bidirectional"))
      (node (ref "IC3") (pin "1") (pinfunction "A0_1") (pintype "bidirectional"))
    )
    (net (code "109") (name "Net-(IC20-W)") (class "Default")
      (node (ref "IC20") (pin "1") (pinfunction "W_1") (pintype "bidirectional"))
      (node (ref "IC4") (pin "1") (pinfunction "A0_1") (pintype "bidirectional"))
    )
    (net (code "110") (name "Net-(J1-PadA46)") (class "Default")
      (node (ref "J1") (pin "A46") (pinfunction "A46_A46") (pintype "bidirectional"))
      (node (ref "J1") (pin "A48") (pinfunction "A48_A48") (pintype "bidirectional"))
    )
    (net (code "111") (name "Net-(J1-PadB1)") (class "Default")
      (node (ref "J1") (pin "B1") (pinfunction "B1_B1") (pintype "bidirectional"))
      (node (ref "R9") (pin "2") (pinfunction "2_2") (pintype "passive"))
    )
    (net (code "112") (name "unconnected-(IC5-N{slash}C-Pad1)") (class "Default")
      (node (ref "IC5") (pin "1") (pinfunction "N/C_1") (pintype "bidirectional"))
    )
    (net (code "113") (name "unconnected-(IC6-N{slash}C-Pad1)") (class "Default")
      (node (ref "IC6") (pin "1") (pinfunction "N/C_1") (pintype "bidirectional"))
    )
    (net (code "114") (name "unconnected-(IC7-N{slash}C-Pad1)") (class "Default")
      (node (ref "IC7") (pin "1") (pinfunction "N/C_1") (pintype "bidirectional"))
    )
    (net (code "115") (name "unconnected-(IC8-N{slash}C-Pad1)") (class "Default")
      (node (ref "IC8") (pin "1") (pinfunction "N/C_1") (pintype "bidirectional"))
    )
    (net (code "116") (name "unconnected-(IC9-GND-Pad4)") (class "Default")
      (node (ref "IC9") (pin "4") (pinfunction "GND_4") (pintype "passive"))
    )
    (net (code "117") (name "unconnected-(IC10-N{slash}C-Pad1)") (class "Default")
      (node (ref "IC10") (pin "1") (pinfunction "N/C_1") (pintype "bidirectional"))
    )
    (net (code "118") (name "unconnected-(IC11-GND-Pad4)") (class "Default")
      (node (ref "IC11") (pin "4") (pinfunction "GND_4") (pintype "passive"))
    )
    (net (code "119") (name "unconnected-(IC13-N{slash}C-Pad1)") (class "Default")
      (node (ref "IC13") (pin "1") (pinfunction "N/C_1") (pintype "bidirectional"))
    )
    (net (code "120") (name "unconnected-(IC14-+INB-Pad5)") (class "Default")
      (node (ref "IC14") (pin "5") (pinfunction "+INB_5") (pintype "bidirectional"))
    )
    (net (code "121") (name "unconnected-(IC14--INB-Pad6)") (class "Default")
      (node (ref "IC14") (pin "6") (pinfunction "-INB_6") (pintype "bidirectional"))
    )
    (net (code "122") (name "unconnected-(IC14-OUTB-Pad7)") (class "Default")
      (node (ref "IC14") (pin "7") (pinfunction "OUTB_7") (pintype "bidirectional"))
    )
    (net (code "123") (name "unconnected-(IC16-N{slash}C-Pad1)") (class "Default")
      (node (ref "IC16") (pin "1") (pinfunction "N/C_1") (pintype "bidirectional"))
    )
    (net (code "124") (name "unconnected-(IC17-N{slash}C-Pad1)") (class "Default")
      (node (ref "IC17") (pin "1") (pinfunction "N/C_1") (pintype "bidirectional"))
    )
    (net (code "125") (name "unconnected-(J1-PadA1)") (class "Default")
      (node (ref "J1") (pin "A1") (pinfunction "A1_A1") (pintype "bidirectional"))
    )
    (net (code "126") (name "unconnected-(J1-PadA2)") (class "Default")
      (node (ref "J1") (pin "A2") (pinfunction "A2_A2") (pintype "bidirectional"))
    )
    (net (code "127") (name "unconnected-(J1-PadA3)") (class "Default")
      (node (ref "J1") (pin "A3") (pinfunction "A3_A3") (pintype "bidirectional"))
    )
    (net (code "128") (name "unconnected-(J1-PadA4)") (class "Default")
      (node (ref "J1") (pin "A4") (pinfunction "A4_A4") (pintype "bidirectional"))
    )
    (net (code "129") (name "unconnected-(J1-PadA5)") (class "Default")
      (node (ref "J1") (pin "A5") (pinfunction "A5_A5") (pintype "bidirectional"))
    )
    (net (code "130") (name "unconnected-(J1-PadA23)") (class "Default")
      (node (ref "J1") (pin "A23") (pinfunction "A23_A23") (pintype "bidirectional"))
    )
    (net (code "131") (name "unconnected-(J1-PadA29)") (class "Default")
      (node (ref "J1") (pin "A29") (pinfunction "A29_A29") (pintype "bidirectional"))
    )
    (net (code "132") (name "unconnected-(J1-PadA33)") (class "Default")
      (node (ref "J1") (pin "A33") (pinfunction "A33_A33") (pintype "bidirectional"))
    )
    (net (code "133") (name "unconnected-(J1-PadA37)") (class "Default")
      (node (ref "J1") (pin "A37") (pinfunction "A37_A37") (pintype "bidirectional"))
    )
    (net (code "134") (name "unconnected-(J1-PadA41)") (class "Default")
      (node (ref "J1") (pin "A41") (pinfunction "A41_A41") (pintype "bidirectional"))
    )
    (net (code "135") (name "unconnected-(J1-PadA43)") (class "Default")
      (node (ref "J1") (pin "A43") (pinfunction "A43_A43") (pintype "bidirectional"))
    )
    (net (code "136") (name "unconnected-(J1-PadA45)") (class "Default")
      (node (ref "J1") (pin "A45") (pinfunction "A45_A45") (pintype "bidirectional"))
    )
    (net (code "137") (name "unconnected-(J1-PadA47)") (class "Default")
      (node (ref "J1") (pin "A47") (pinfunction "A47_A47") (pintype "bidirectional"))
    )
    (net (code "138") (name "unconnected-(J1-PadA49)") (class "Default")
      (node (ref "J1") (pin "A49") (pinfunction "A49_A49") (pintype "bidirectional"))
    )
    (net (code "139") (name "unconnected-(J1-PadA50)") (class "Default")
      (node (ref "J1") (pin "A50") (pinfunction "A50_A50") (pintype "bidirectional"))
    )
    (net (code "140") (name "unconnected-(J1-PadB3)") (class "Default")
      (node (ref "J1") (pin "B3") (pinfunction "B3_B3") (pintype "bidirectional"))
    )
    (net (code "141") (name "unconnected-(J1-PadB4)") (class "Default")
      (node (ref "J1") (pin "B4") (pinfunction "B4_B4") (pintype "bidirectional"))
    )
    (net (code "142") (name "unconnected-(J1-PadB46)") (class "Default")
      (node (ref "J1") (pin "B46") (pinfunction "B46_B46") (pintype "bidirectional"))
    )
    (net (code "143") (name "unconnected-(J1-PadB48)") (class "Default")
      (node (ref "J1") (pin "B48") (pinfunction "B48_B48") (pintype "bidirectional"))
    )
    (net (code "144") (name "unconnected-(J1-PadB49)") (class "Default")
      (node (ref "J1") (pin "B49") (pinfunction "B49_B49") (pintype "bidirectional"))
    )
  )
)
